# controller.net
KiCad netlist of a schematic drawn in EAGLE
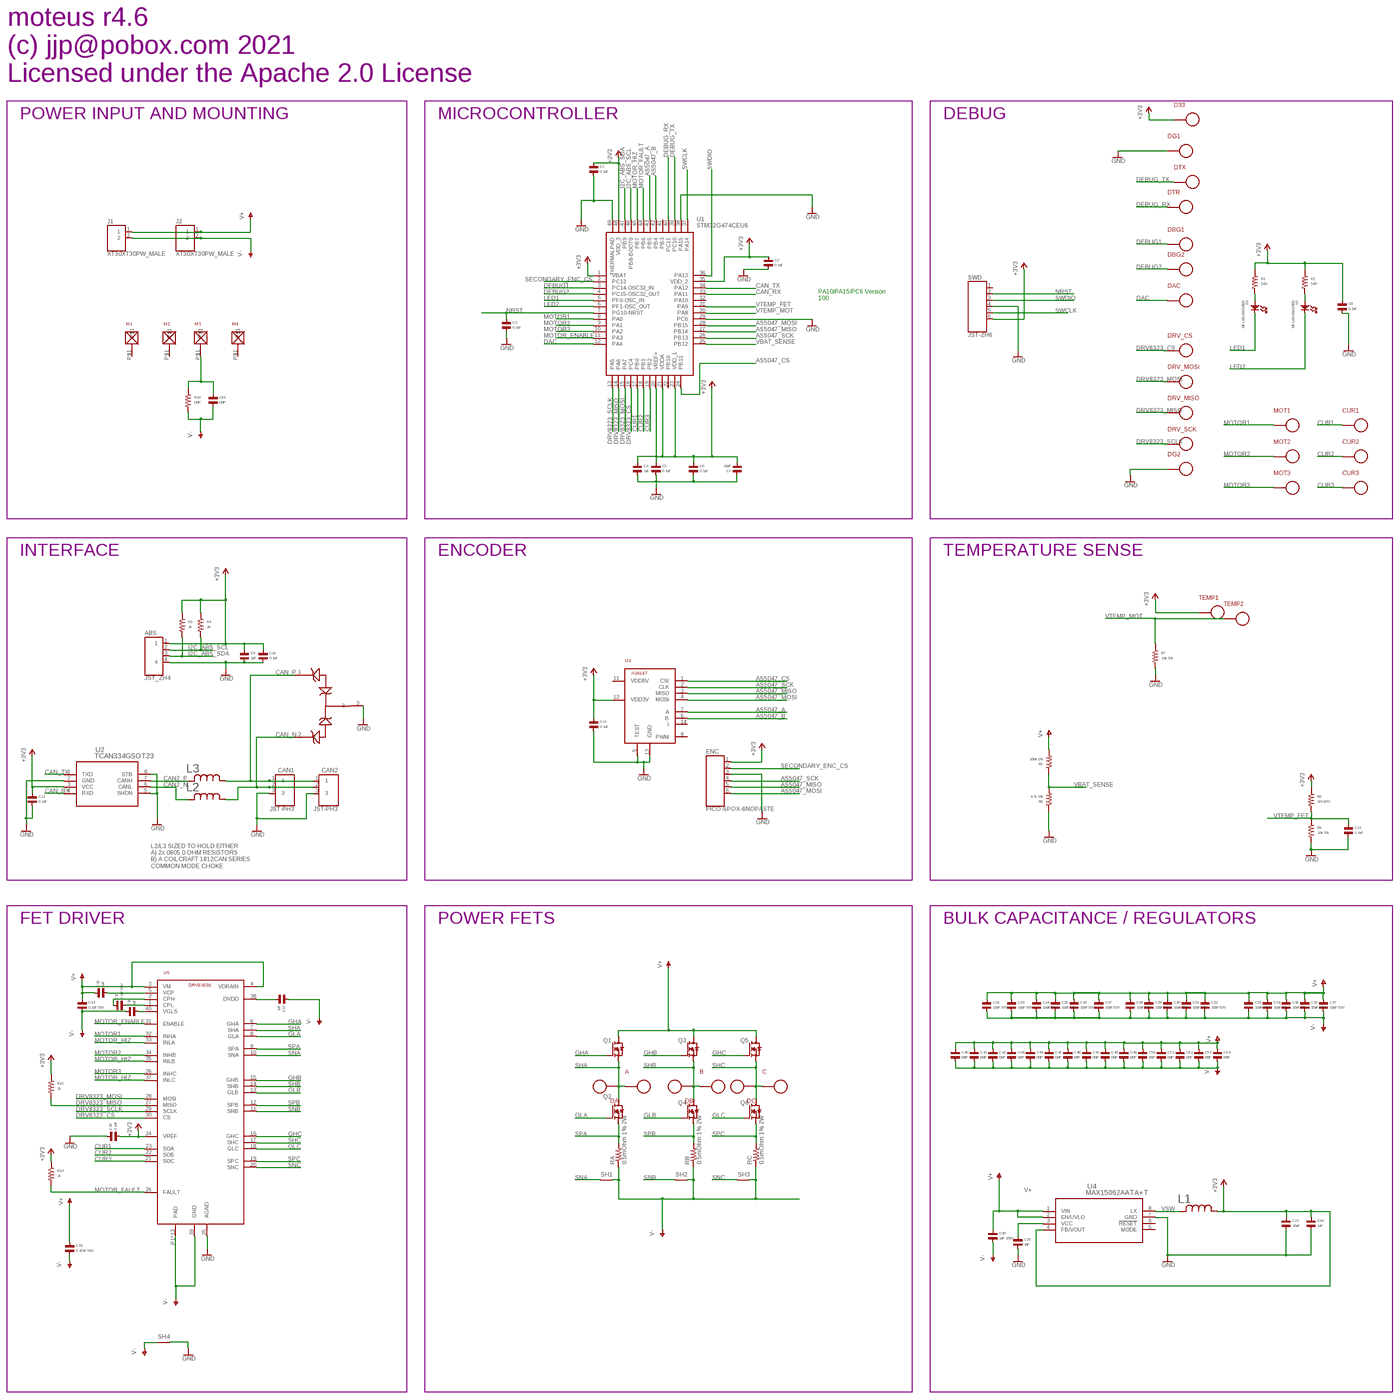
[diagram p0: schematic, sheet 1, overview]
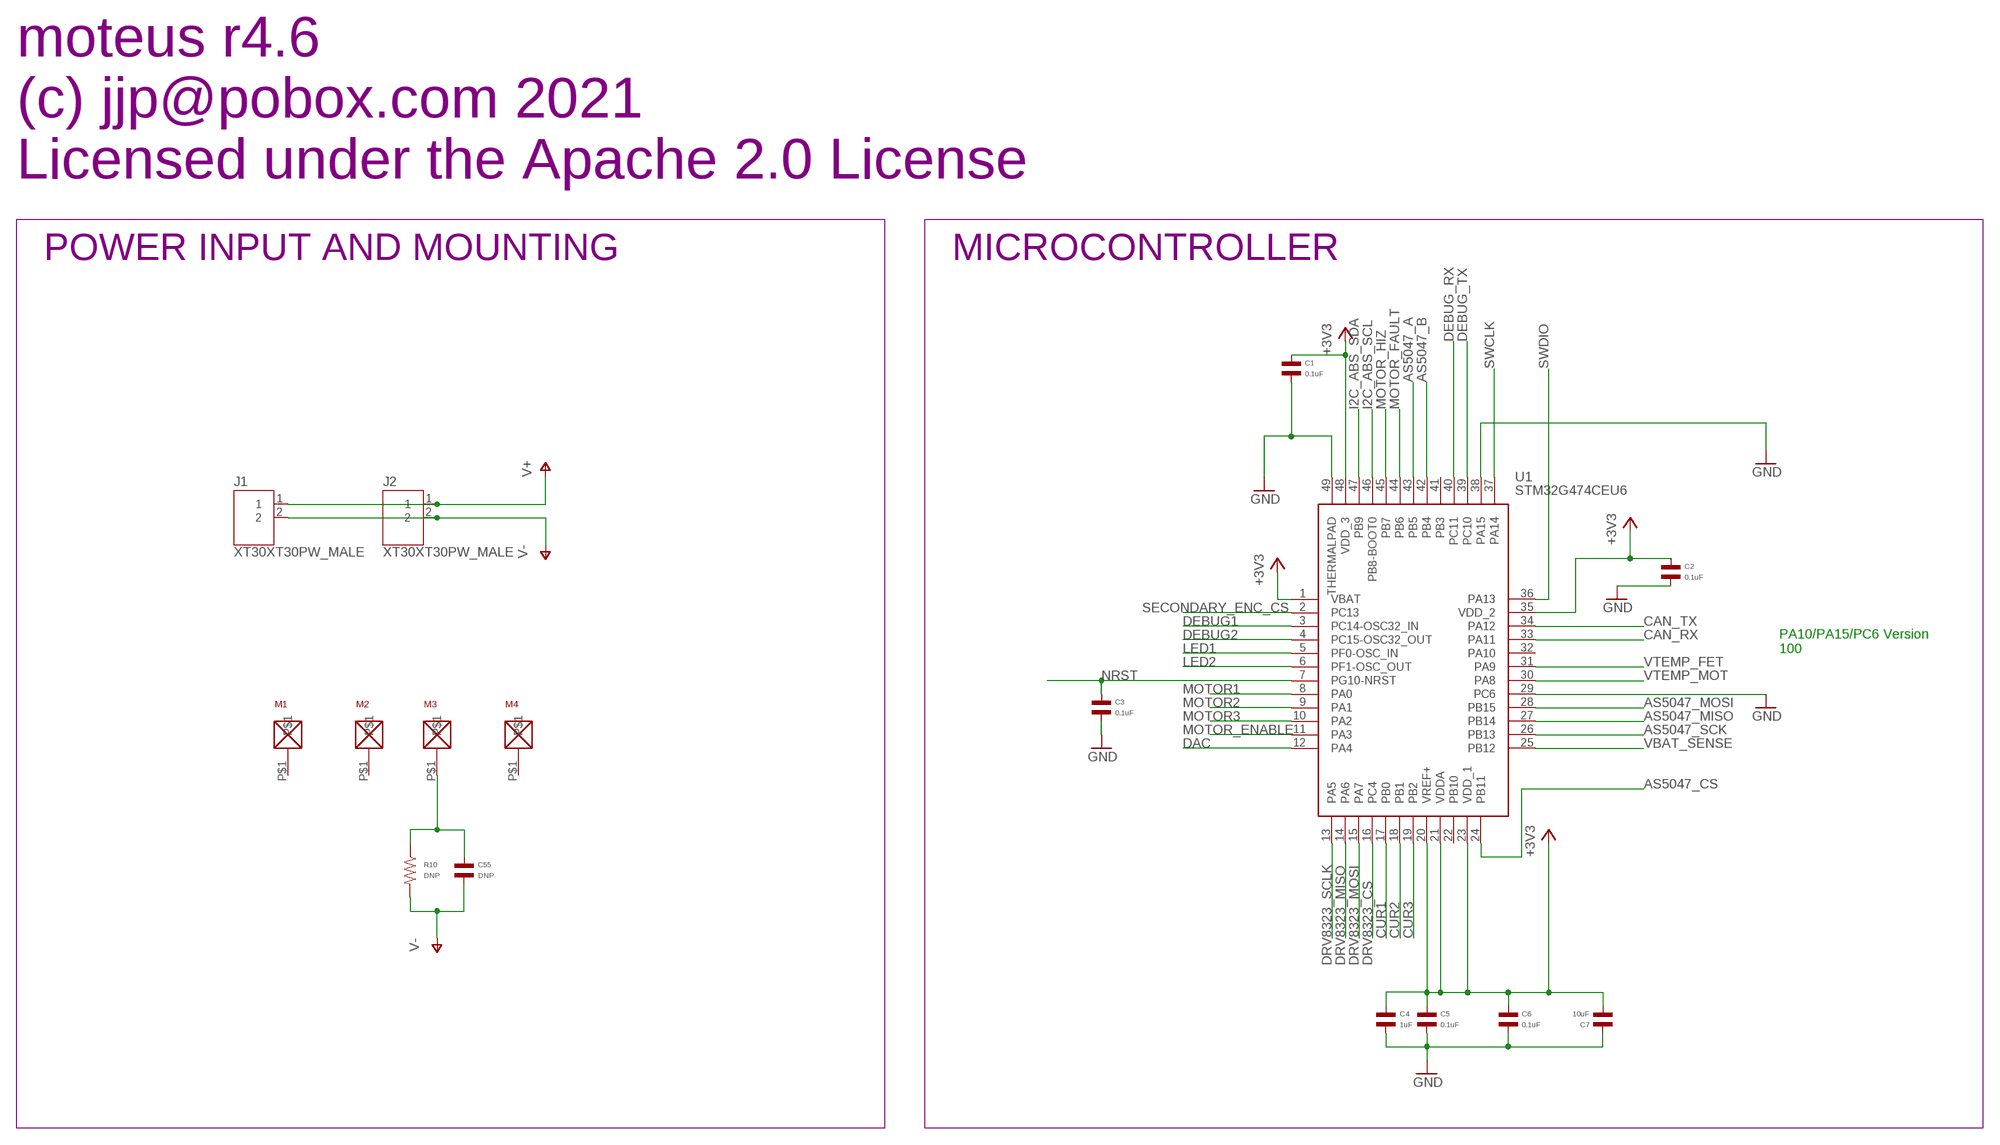
[diagram p1: schematic, sheet 1, part 1 of 4]
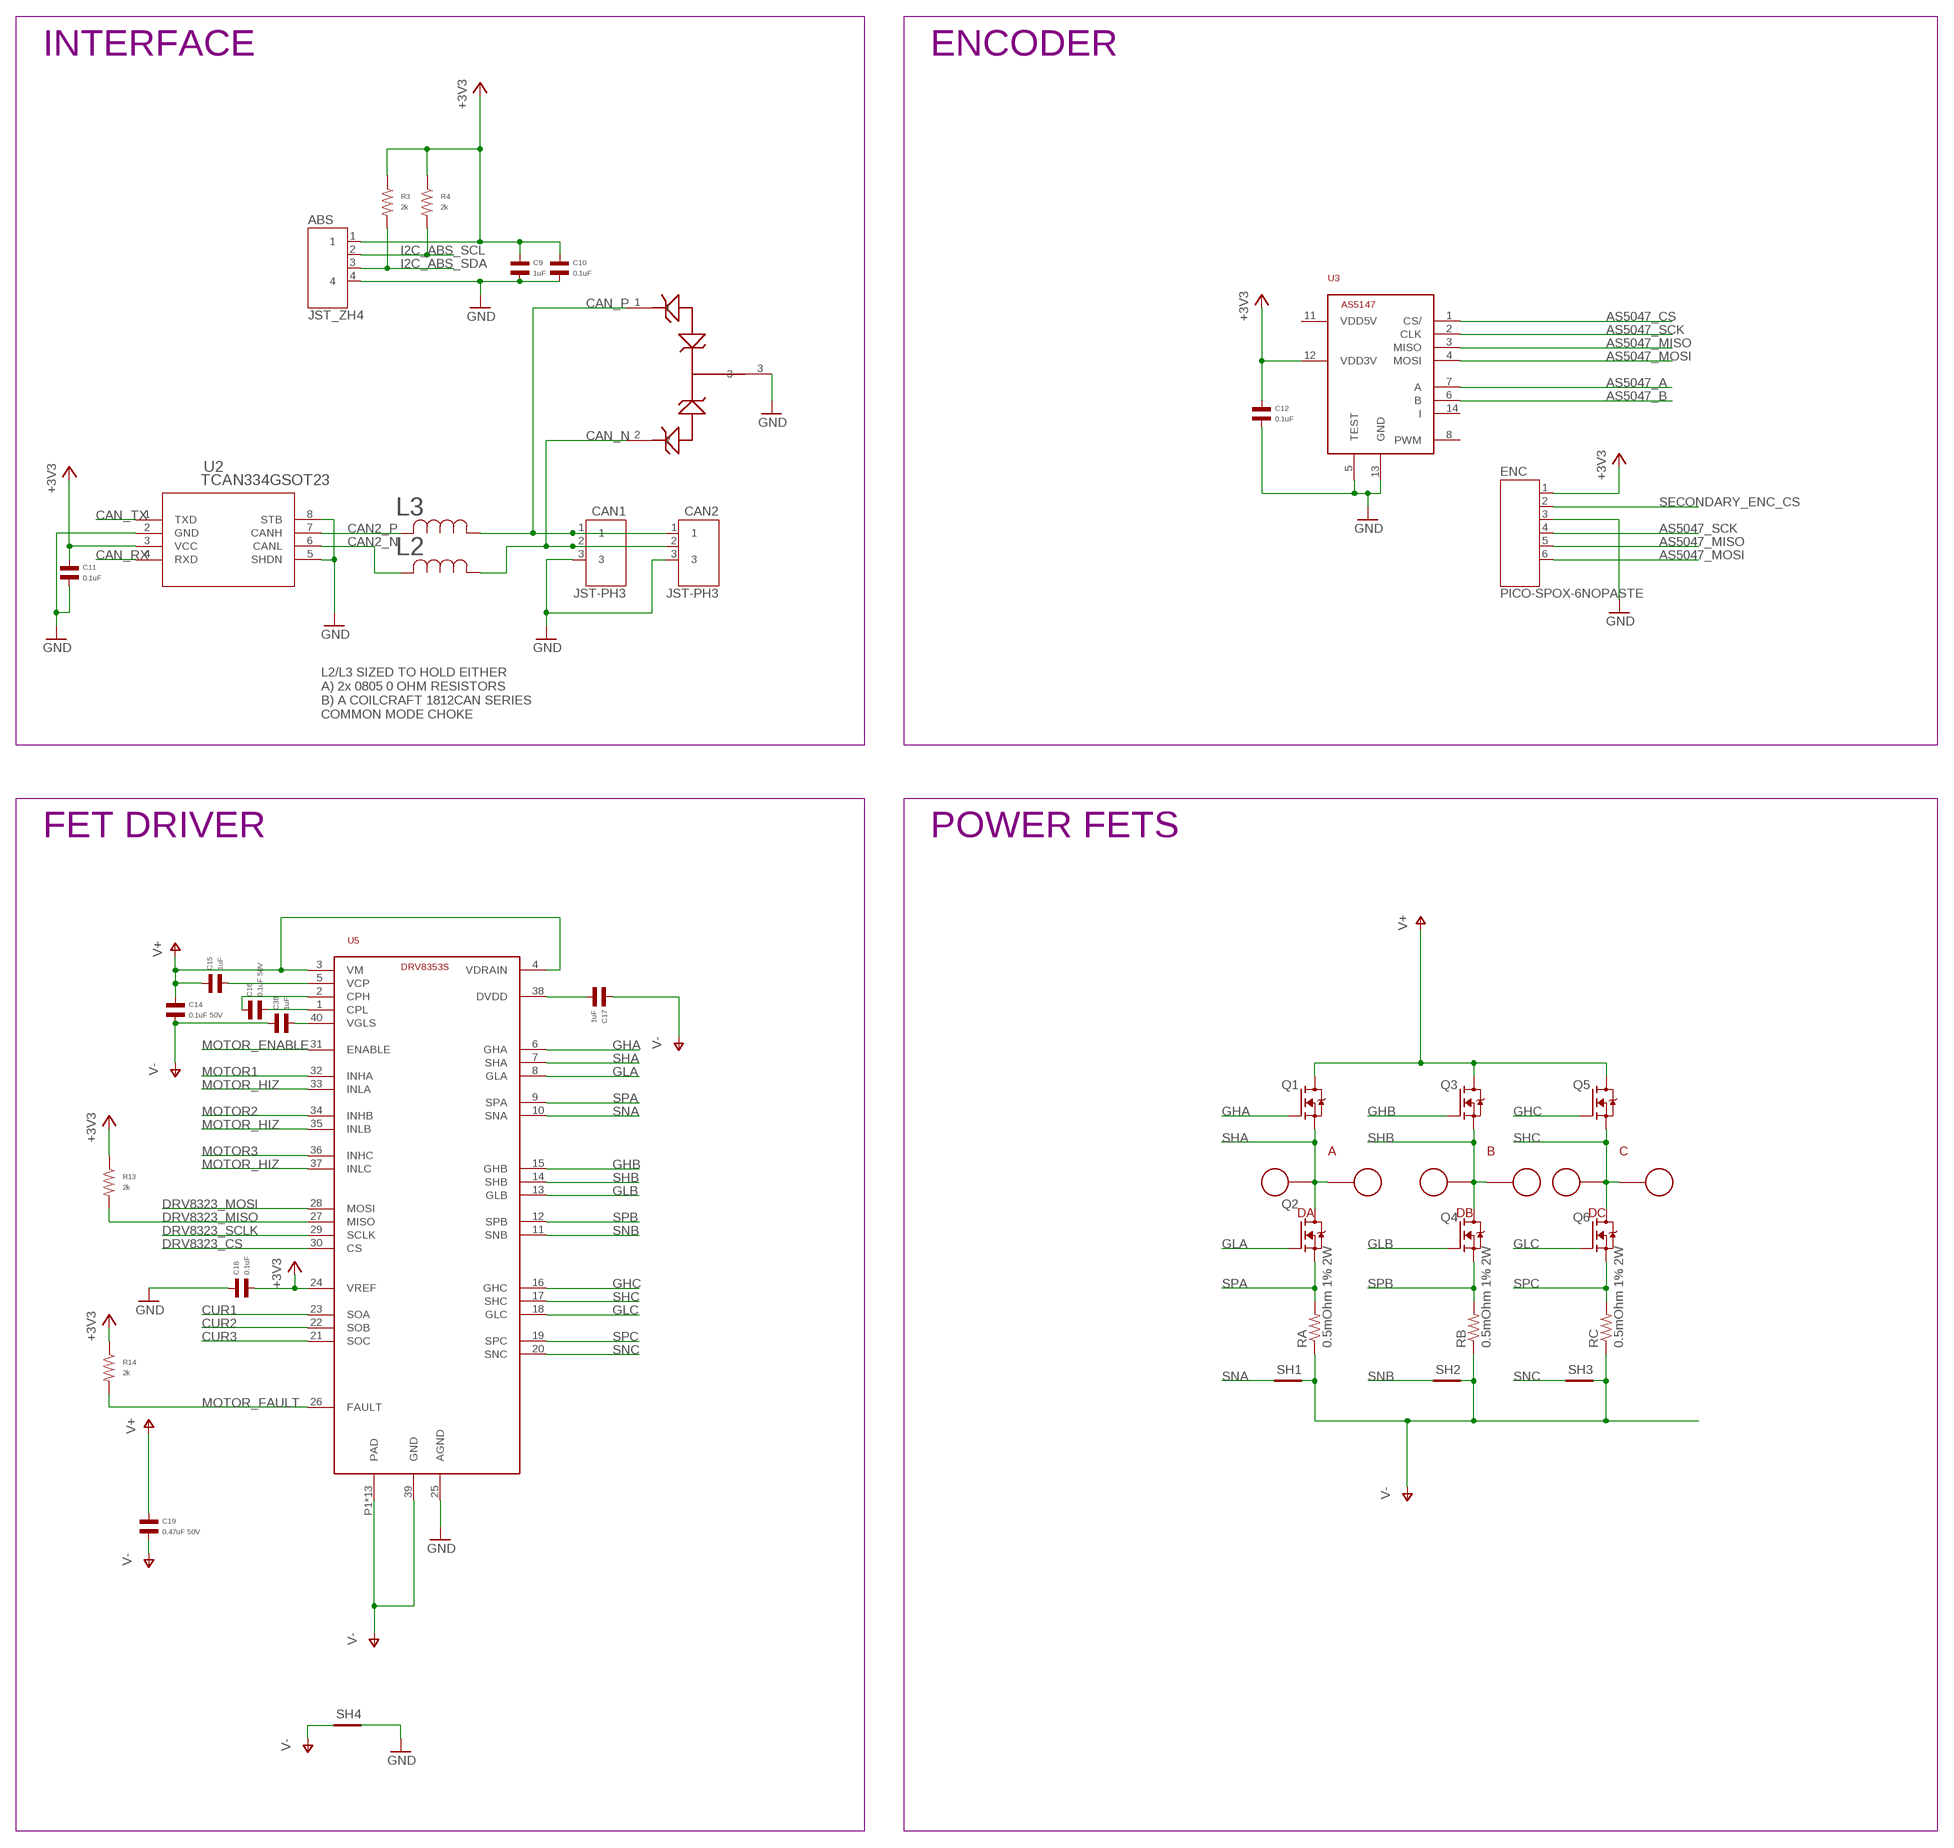
[diagram p2: schematic, sheet 1, part 2 of 4]
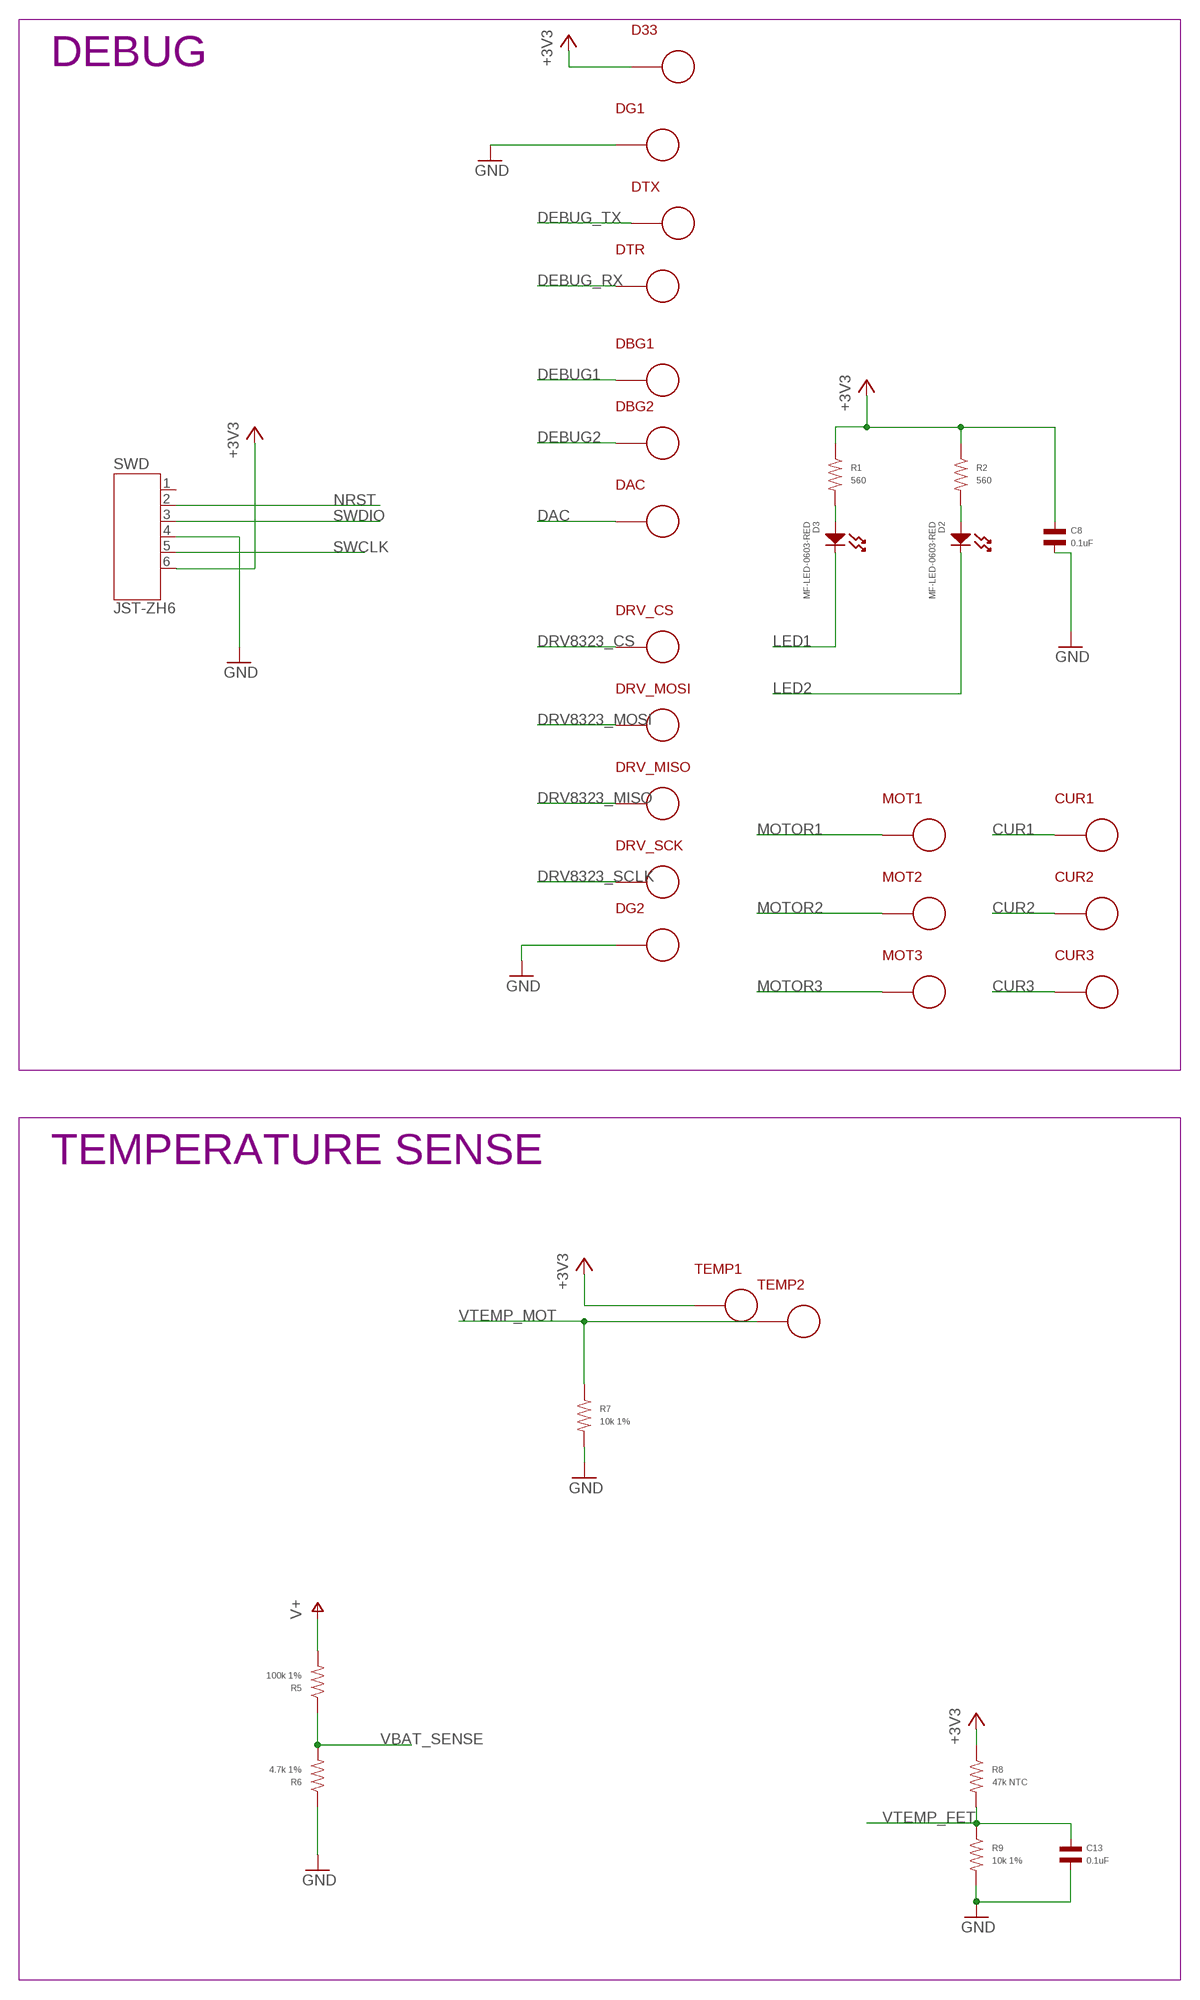
[diagram p3: schematic, sheet 1, part 3 of 4]
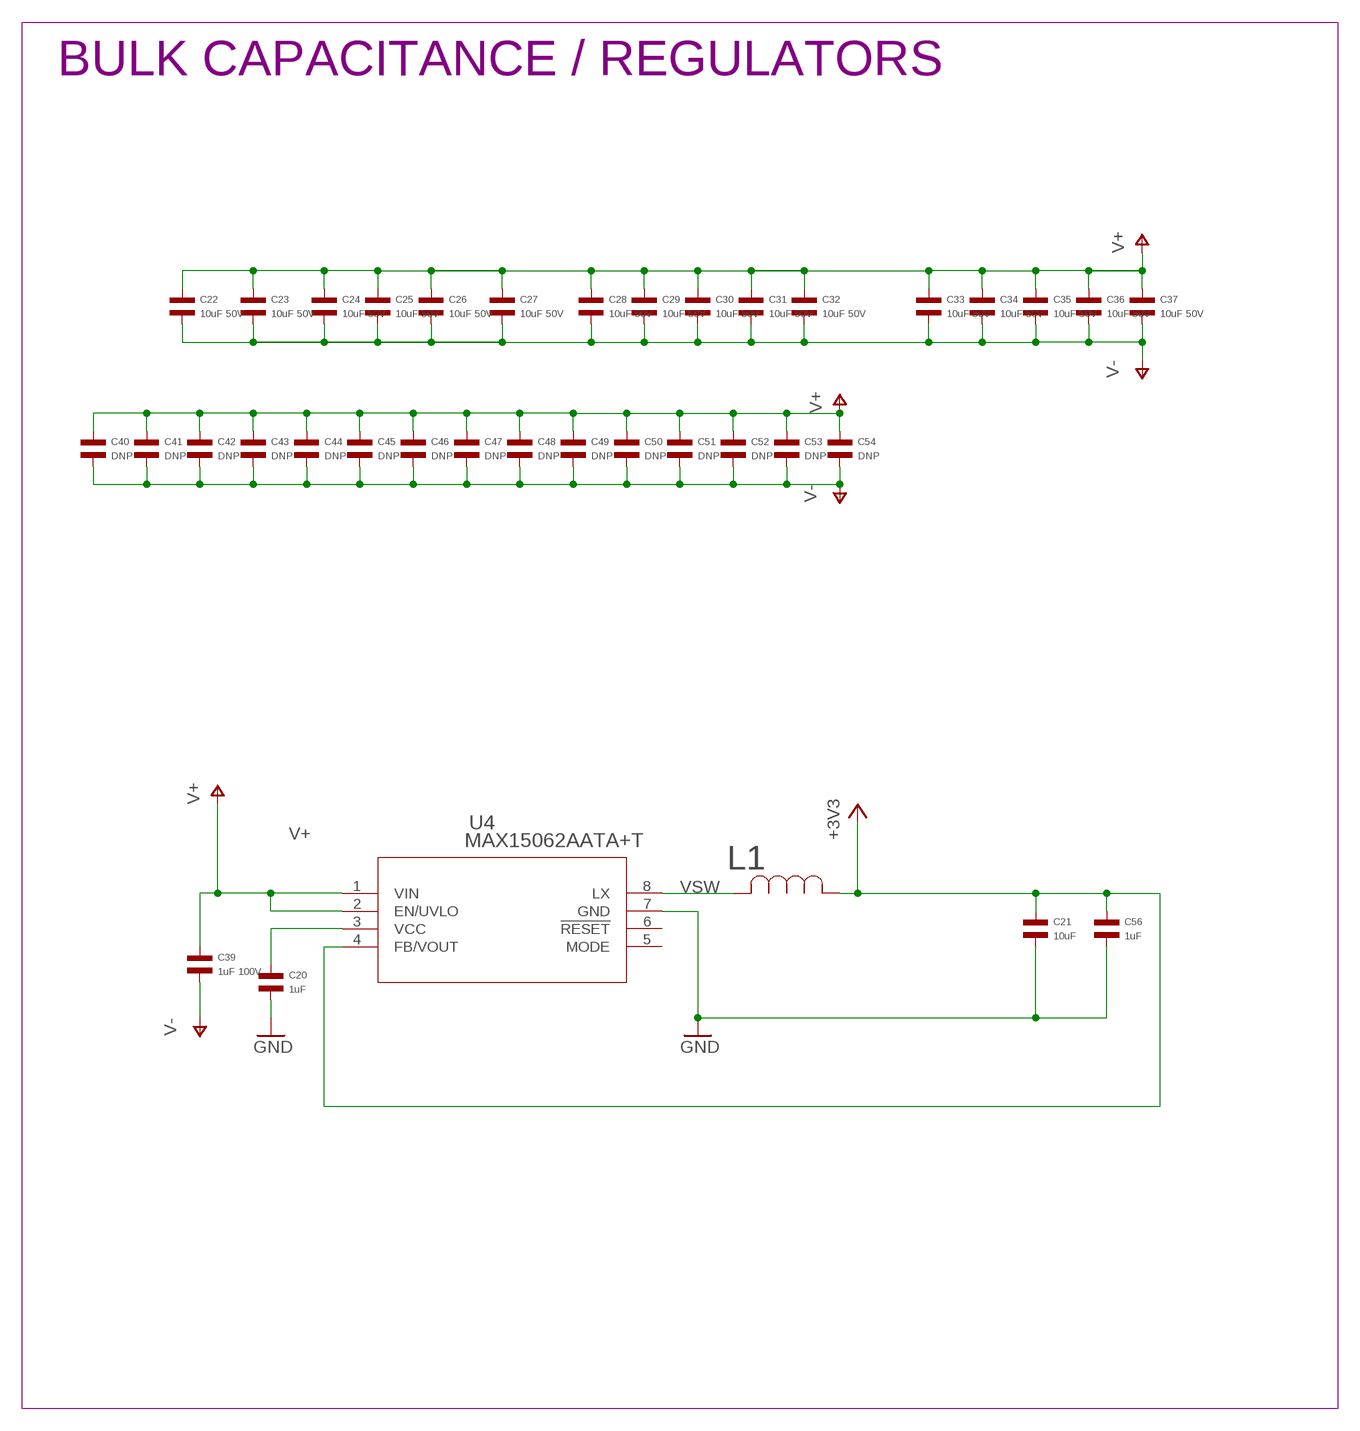
[diagram p4: schematic, sheet 1, part 4 of 4]

(export (version "E")
  (design (tool "Eeschema 10.0.6"))
  (components
    (comp (ref "A")
      (value "PAD16AWG_PAD")
      (footprint "eagle-import:16AWG_PAD")
      (libsource (lib "eagle-import") (part "PAD16AWG_PAD"))
    )
    (comp (ref "ABS")
      (value "JST_ZH4")
      (footprint "eagle-import:JST_S4B-ZR-SM4A-TF(LF)(SN)")
      (fields (field (name "MF") "JST") (field (name "MPN") "S4B-ZR-SM4A-TF(LF)(SN)"))
      (libsource (lib "eagle-import") (part "JST_ZH4"))
    )
    (comp (ref "B")
      (value "PAD16AWG_PAD")
      (footprint "eagle-import:16AWG_PAD")
      (libsource (lib "eagle-import") (part "PAD16AWG_PAD"))
    )
    (comp (ref "C")
      (value "PAD16AWG_PAD")
      (footprint "eagle-import:16AWG_PAD")
      (libsource (lib "eagle-import") (part "PAD16AWG_PAD"))
    )
    (comp (ref "C1")
      (value "0.1uF")
      (footprint "eagle-import:C0402")
      (fields (field (name "HOUSEPART") "YES") (field (name "MPN") "MF-CAP-0402-0.1uF"))
      (libsource (lib "eagle-import") (part "mfpassives_CAPACITOR_NP_0402"))
    )
    (comp (ref "C2")
      (value "0.1uF")
      (footprint "eagle-import:C0402")
      (fields (field (name "HOUSEPART") "YES") (field (name "MPN") "MF-CAP-0402-0.1uF"))
      (libsource (lib "eagle-import") (part "mfpassives_CAPACITOR_NP_0402"))
    )
    (comp (ref "C3")
      (value "0.1uF")
      (footprint "eagle-import:C0402")
      (fields (field (name "HOUSEPART") "YES") (field (name "MPN") "MF-CAP-0402-0.1uF"))
      (libsource (lib "eagle-import") (part "mfpassives_CAPACITOR_NP_0402"))
    )
    (comp (ref "C4")
      (value "1uF")
      (footprint "eagle-import:C0402")
      (fields (field (name "HOUSEPART") "YES") (field (name "MPN") "MF-CAP-0402-1uF"))
      (libsource (lib "eagle-import") (part "mfpassives_CAPACITOR_NP_0402"))
    )
    (comp (ref "C5")
      (value "0.1uF")
      (footprint "eagle-import:C0402")
      (fields (field (name "HOUSEPART") "YES") (field (name "MPN") "MF-CAP-0402-0.1uF"))
      (libsource (lib "eagle-import") (part "mfpassives_CAPACITOR_NP_0402"))
    )
    (comp (ref "C6")
      (value "0.1uF")
      (footprint "eagle-import:C0402")
      (fields (field (name "HOUSEPART") "YES") (field (name "MPN") "MF-CAP-0402-0.1uF"))
      (libsource (lib "eagle-import") (part "mfpassives_CAPACITOR_NP_0402"))
    )
    (comp (ref "C7")
      (value "10uF")
      (footprint "eagle-import:C1206")
      (fields (field (name "HOUSEPART") "YES") (field (name "MPN") "MF-CAP-1206-10uF"))
      (libsource (lib "eagle-import") (part "mfpassives_CAPACITOR_NP_1206"))
    )
    (comp (ref "C8")
      (value "0.1uF")
      (footprint "eagle-import:C0402")
      (fields (field (name "HOUSEPART") "YES") (field (name "MPN") "MF-CAP-0402-0.1uF"))
      (libsource (lib "eagle-import") (part "mfpassives_CAPACITOR_NP_0402"))
    )
    (comp (ref "C9")
      (value "1uF")
      (footprint "eagle-import:C0402")
      (fields (field (name "HOUSEPART") "YES") (field (name "MPN") "MF-CAP-0402-1uF"))
      (libsource (lib "eagle-import") (part "mfpassives_CAPACITOR_NP_0402"))
    )
    (comp (ref "C10")
      (value "0.1uF")
      (footprint "eagle-import:C0402")
      (fields (field (name "HOUSEPART") "YES") (field (name "MPN") "MF-CAP-0402-0.1uF"))
      (libsource (lib "eagle-import") (part "mfpassives_CAPACITOR_NP_0402"))
    )
    (comp (ref "C11")
      (value "0.1uF")
      (footprint "eagle-import:C0402")
      (fields (field (name "HOUSEPART") "YES") (field (name "MPN") "MF-CAP-0402-0.1uF"))
      (libsource (lib "eagle-import") (part "mfpassives_CAPACITOR_NP_0402"))
    )
    (comp (ref "C12")
      (value "0.1uF")
      (footprint "eagle-import:C0402")
      (fields (field (name "HOUSEPART") "YES") (field (name "MPN") "MF-CAP-0402-0.1uF"))
      (libsource (lib "eagle-import") (part "mfpassives_CAPACITOR_NP_0402"))
    )
    (comp (ref "C13")
      (value "0.1uF")
      (footprint "eagle-import:C0402")
      (fields (field (name "HOUSEPART") "YES") (field (name "MPN") "MF-CAP-0402-0.1uF"))
      (libsource (lib "eagle-import") (part "mfpassives_CAPACITOR_NP_0402"))
    )
    (comp (ref "C14")
      (value "0.1uF 50V")
      (footprint "eagle-import:C0402")
      (fields (field (name "MF") "TDK") (field (name "MPN") "CGA2B3X7R1H104K050BB"))
      (libsource (lib "eagle-import") (part "mfpassives_CAPACITOR_NP_0402"))
    )
    (comp (ref "C15")
      (value "1uF")
      (footprint "eagle-import:C0402")
      (fields (field (name "HOUSEPART") "YES") (field (name "MPN") "MF-CAP-0402-1uF"))
      (libsource (lib "eagle-import") (part "mfpassives_CAPACITOR_NP_0402"))
    )
    (comp (ref "C16")
      (value "0.1uF 50V")
      (footprint "eagle-import:C0402")
      (fields (field (name "MF") "TDK") (field (name "MPN") "CGA2B3X7R1H104K050BB"))
      (libsource (lib "eagle-import") (part "mfpassives_CAPACITOR_NP_0402"))
    )
    (comp (ref "C17")
      (value "1uF")
      (footprint "eagle-import:C0402")
      (fields (field (name "HOUSEPART") "YES") (field (name "MPN") "MF-CAP-0402-1uF"))
      (libsource (lib "eagle-import") (part "mfpassives_CAPACITOR_NP_0402"))
    )
    (comp (ref "C18")
      (value "0.1uF")
      (footprint "eagle-import:C0402")
      (fields (field (name "HOUSEPART") "YES") (field (name "MPN") "MF-CAP-0402-0.1uF"))
      (libsource (lib "eagle-import") (part "mfpassives_CAPACITOR_NP_0402"))
    )
    (comp (ref "C19")
      (value "0.47uF 50V")
      (footprint "eagle-import:C0402")
      (fields (field (name "MF") "Murata") (field (name "MPN") "GRM155R61H474KE11D"))
      (libsource (lib "eagle-import") (part "mfpassives_CAPACITOR_NP_0402"))
    )
    (comp (ref "C20")
      (value "1uF")
      (footprint "eagle-import:C0603")
      (fields (field (name "HOUSEPART") "1") (field (name "MPN") "MF-CAP-0603-1uF"))
      (libsource (lib "eagle-import") (part "mfpassives_CAPACITOR_NP_0603"))
    )
    (comp (ref "C21")
      (value "10uF")
      (footprint "eagle-import:C1206")
      (fields (field (name "HOUSEPART") "1") (field (name "MPN") "MF-CAP-1206-10uF"))
      (libsource (lib "eagle-import") (part "mfpassives_CAPACITOR_NP_1206"))
    )
    (comp (ref "C22")
      (value "10uF 50V")
      (footprint "eagle-import:C1206")
      (fields (field (name "MF") "TDK") (field (name "MPN") "C3216X7R1H106K160AE"))
      (libsource (lib "eagle-import") (part "mfpassives_CAPACITOR_NP_1206"))
    )
    (comp (ref "C23")
      (value "10uF 50V")
      (footprint "eagle-import:C1206")
      (fields (field (name "MF") "TDK") (field (name "MPN") "C3216X7R1H106K160AE"))
      (libsource (lib "eagle-import") (part "mfpassives_CAPACITOR_NP_1206"))
    )
    (comp (ref "C24")
      (value "10uF 50V")
      (footprint "eagle-import:C1206")
      (fields (field (name "MF") "TDK") (field (name "MPN") "C3216X7R1H106K160AE"))
      (libsource (lib "eagle-import") (part "mfpassives_CAPACITOR_NP_1206"))
    )
    (comp (ref "C25")
      (value "10uF 50V")
      (footprint "eagle-import:C1206")
      (fields (field (name "MF") "TDK") (field (name "MPN") "C3216X7R1H106K160AE"))
      (libsource (lib "eagle-import") (part "mfpassives_CAPACITOR_NP_1206"))
    )
    (comp (ref "C26")
      (value "10uF 50V")
      (footprint "eagle-import:C1206")
      (fields (field (name "MF") "TDK") (field (name "MPN") "C3216X7R1H106K160AE"))
      (libsource (lib "eagle-import") (part "mfpassives_CAPACITOR_NP_1206"))
    )
    (comp (ref "C27")
      (value "10uF 50V")
      (footprint "eagle-import:C1206")
      (fields (field (name "MF") "TDK") (field (name "MPN") "C3216X7R1H106K160AE"))
      (libsource (lib "eagle-import") (part "mfpassives_CAPACITOR_NP_1206"))
    )
    (comp (ref "C28")
      (value "10uF 50V")
      (footprint "eagle-import:C1206")
      (fields (field (name "MF") "TDK") (field (name "MPN") "C3216X7R1H106K160AE"))
      (libsource (lib "eagle-import") (part "mfpassives_CAPACITOR_NP_1206"))
    )
    (comp (ref "C29")
      (value "10uF 50V")
      (footprint "eagle-import:C1206")
      (fields (field (name "MF") "TDK") (field (name "MPN") "C3216X7R1H106K160AE"))
      (libsource (lib "eagle-import") (part "mfpassives_CAPACITOR_NP_1206"))
    )
    (comp (ref "C30")
      (value "10uF 50V")
      (footprint "eagle-import:C1206")
      (fields (field (name "MF") "TDK") (field (name "MPN") "C3216X7R1H106K160AE"))
      (libsource (lib "eagle-import") (part "mfpassives_CAPACITOR_NP_1206"))
    )
    (comp (ref "C31")
      (value "10uF 50V")
      (footprint "eagle-import:C1206")
      (fields (field (name "MF") "TDK") (field (name "MPN") "C3216X7R1H106K160AE"))
      (libsource (lib "eagle-import") (part "mfpassives_CAPACITOR_NP_1206"))
    )
    (comp (ref "C32")
      (value "10uF 50V")
      (footprint "eagle-import:C1206")
      (fields (field (name "MF") "TDK") (field (name "MPN") "C3216X7R1H106K160AE"))
      (libsource (lib "eagle-import") (part "mfpassives_CAPACITOR_NP_1206"))
    )
    (comp (ref "C33")
      (value "10uF 50V")
      (footprint "eagle-import:C1206")
      (fields (field (name "MF") "TDK") (field (name "MPN") "C3216X7R1H106K160AE"))
      (libsource (lib "eagle-import") (part "mfpassives_CAPACITOR_NP_1206"))
    )
    (comp (ref "C34")
      (value "10uF 50V")
      (footprint "eagle-import:C1206")
      (fields (field (name "MF") "TDK") (field (name "MPN") "C3216X7R1H106K160AE"))
      (libsource (lib "eagle-import") (part "mfpassives_CAPACITOR_NP_1206"))
    )
    (comp (ref "C35")
      (value "10uF 50V")
      (footprint "eagle-import:C1206")
      (fields (field (name "MF") "TDK") (field (name "MPN") "C3216X7R1H106K160AE"))
      (libsource (lib "eagle-import") (part "mfpassives_CAPACITOR_NP_1206"))
    )
    (comp (ref "C36")
      (value "10uF 50V")
      (footprint "eagle-import:C1206")
      (fields (field (name "MF") "TDK") (field (name "MPN") "C3216X7R1H106K160AE"))
      (libsource (lib "eagle-import") (part "mfpassives_CAPACITOR_NP_1206"))
    )
    (comp (ref "C37")
      (value "10uF 50V")
      (footprint "eagle-import:C1206")
      (fields (field (name "MF") "TDK") (field (name "MPN") "C3216X7R1H106K160AE"))
      (libsource (lib "eagle-import") (part "mfpassives_CAPACITOR_NP_1206"))
    )
    (comp (ref "C38")
      (value "1uF")
      (footprint "eagle-import:C0402")
      (fields (field (name "HOUSEPART") "YES") (field (name "MPN") "MF-CAP-0402-1uF"))
      (libsource (lib "eagle-import") (part "mfpassives_CAPACITOR_NP_0402"))
    )
    (comp (ref "C39")
      (value "1uF 100V")
      (footprint "eagle-import:C0805")
      (fields (field (name "MF") "MURATA") (field (name "MPN") "GCM21BC72A105KE36L"))
      (libsource (lib "eagle-import") (part "mfpassives_CAPACITOR_NP_0805"))
    )
    (comp (ref "C40")
      (value "DNP")
      (footprint "eagle-import:C1206_NOCREAM")
      (libsource (lib "eagle-import") (part "CAPACITOR_NP_1206_NOCREAM"))
    )
    (comp (ref "C41")
      (value "DNP")
      (footprint "eagle-import:C1206_NOCREAM")
      (libsource (lib "eagle-import") (part "CAPACITOR_NP_1206_NOCREAM"))
    )
    (comp (ref "C42")
      (value "DNP")
      (footprint "eagle-import:C1206_NOCREAM")
      (libsource (lib "eagle-import") (part "CAPACITOR_NP_1206_NOCREAM"))
    )
    (comp (ref "C43")
      (value "DNP")
      (footprint "eagle-import:C1206_NOCREAM")
      (libsource (lib "eagle-import") (part "CAPACITOR_NP_1206_NOCREAM"))
    )
    (comp (ref "C44")
      (value "DNP")
      (footprint "eagle-import:C1206_NOCREAM")
      (libsource (lib "eagle-import") (part "CAPACITOR_NP_1206_NOCREAM"))
    )
    (comp (ref "C45")
      (value "DNP")
      (footprint "eagle-import:C1206_NOCREAM")
      (libsource (lib "eagle-import") (part "CAPACITOR_NP_1206_NOCREAM"))
    )
    (comp (ref "C46")
      (value "DNP")
      (footprint "eagle-import:C1206_NOCREAM")
      (libsource (lib "eagle-import") (part "CAPACITOR_NP_1206_NOCREAM"))
    )
    (comp (ref "C47")
      (value "DNP")
      (footprint "eagle-import:C1206_NOCREAM")
      (libsource (lib "eagle-import") (part "CAPACITOR_NP_1206_NOCREAM"))
    )
    (comp (ref "C48")
      (value "DNP")
      (footprint "eagle-import:C1206_NOCREAM")
      (libsource (lib "eagle-import") (part "CAPACITOR_NP_1206_NOCREAM"))
    )
    (comp (ref "C49")
      (value "DNP")
      (footprint "eagle-import:C1206_NOCREAM")
      (libsource (lib "eagle-import") (part "CAPACITOR_NP_1206_NOCREAM"))
    )
    (comp (ref "C50")
      (value "DNP")
      (footprint "eagle-import:C1206_NOCREAM")
      (libsource (lib "eagle-import") (part "CAPACITOR_NP_1206_NOCREAM"))
    )
    (comp (ref "C51")
      (value "DNP")
      (footprint "eagle-import:C1206_NOCREAM")
      (libsource (lib "eagle-import") (part "CAPACITOR_NP_1206_NOCREAM"))
    )
    (comp (ref "C52")
      (value "DNP")
      (footprint "eagle-import:C1206_NOCREAM")
      (libsource (lib "eagle-import") (part "CAPACITOR_NP_1206_NOCREAM"))
    )
    (comp (ref "C53")
      (value "DNP")
      (footprint "eagle-import:C1206_NOCREAM")
      (libsource (lib "eagle-import") (part "CAPACITOR_NP_1206_NOCREAM"))
    )
    (comp (ref "C54")
      (value "DNP")
      (footprint "eagle-import:C1206_NOCREAM")
      (libsource (lib "eagle-import") (part "CAPACITOR_NP_1206_NOCREAM"))
    )
    (comp (ref "C55")
      (value "DNP")
      (footprint "eagle-import:C0402")
      (fields (field (name "POPULATE") "0"))
      (libsource (lib "eagle-import") (part "mfpassives_CAPACITOR_NP_0402"))
    )
    (comp (ref "C56")
      (value "1uF")
      (footprint "eagle-import:C0402")
      (fields (field (name "HOUSEPART") "YES") (field (name "MPN") "MF-CAP-0402-1uF"))
      (libsource (lib "eagle-import") (part "mfpassives_CAPACITOR_NP_0402"))
    )
    (comp (ref "CAN1")
      (value "JST-PH3")
      (footprint "eagle-import:JST_S3B-PH-SM4-TB(LF)(SN)")
      (fields (field (name "MF") "JST") (field (name "MPN") "S3B-PH-SM4-TB(LF)(SN)"))
      (libsource (lib "eagle-import") (part "JST-PH3"))
    )
    (comp (ref "CAN2")
      (value "JST-PH3")
      (footprint "eagle-import:JST_S3B-PH-SM4-TB(LF)(SN)")
      (fields (field (name "MF") "JST") (field (name "MPN") "S3B-PH-SM4-TB(LF)(SN)"))
      (libsource (lib "eagle-import") (part "JST-PH3"))
    )
    (comp (ref "CUR1")
      (value "PAD24AWG_PAD")
      (footprint "eagle-import:24AWG_PAD")
      (libsource (lib "eagle-import") (part "PAD24AWG_PAD"))
    )
    (comp (ref "CUR2")
      (value "PAD24AWG_PAD")
      (footprint "eagle-import:24AWG_PAD")
      (libsource (lib "eagle-import") (part "PAD24AWG_PAD"))
    )
    (comp (ref "CUR3")
      (value "PAD24AWG_PAD")
      (footprint "eagle-import:24AWG_PAD")
      (libsource (lib "eagle-import") (part "PAD24AWG_PAD"))
    )
    (comp (ref "D2")
      (value "MF-LED-0603-RED")
      (footprint "eagle-import:LED0603")
      (fields (field (name "HOUSEPART") "YES") (field (name "MPN") "MF-LED-0603-GREEN"))
      (libsource (lib "eagle-import") (part "LED_SINGLE-0603-RED"))
    )
    (comp (ref "D3")
      (value "MF-LED-0603-RED")
      (footprint "eagle-import:LED0603")
      (fields (field (name "HOUSEPART") "YES"))
      (libsource (lib "eagle-import") (part "LED_SINGLE-0603-RED"))
    )
    (comp (ref "D4")
      (value "DUAL_TVS")
      (footprint "eagle-import:SOT23-3")
      (fields (field (name "MPN") "CDSOT23-0502B"))
      (libsource (lib "eagle-import") (part "DUAL_TVS"))
    )
    (comp (ref "D33")
      (value "PAD24AWG_PAD")
      (footprint "eagle-import:24AWG_PAD")
      (libsource (lib "eagle-import") (part "PAD24AWG_PAD"))
    )
    (comp (ref "DA")
      (value "PAD24AWG_PAD")
      (footprint "eagle-import:24AWG_PAD")
      (libsource (lib "eagle-import") (part "PAD24AWG_PAD"))
    )
    (comp (ref "DAC")
      (value "PAD24AWG_PAD")
      (footprint "eagle-import:24AWG_PAD")
      (libsource (lib "eagle-import") (part "PAD24AWG_PAD"))
    )
    (comp (ref "DB")
      (value "PAD24AWG_PAD")
      (footprint "eagle-import:24AWG_PAD")
      (libsource (lib "eagle-import") (part "PAD24AWG_PAD"))
    )
    (comp (ref "DBG1")
      (value "PAD24AWG_PAD")
      (footprint "eagle-import:24AWG_PAD")
      (libsource (lib "eagle-import") (part "PAD24AWG_PAD"))
    )
    (comp (ref "DBG2")
      (value "PAD24AWG_PAD")
      (footprint "eagle-import:24AWG_PAD")
      (libsource (lib "eagle-import") (part "PAD24AWG_PAD"))
    )
    (comp (ref "DC")
      (value "PAD24AWG_PAD")
      (footprint "eagle-import:24AWG_PAD")
      (libsource (lib "eagle-import") (part "PAD24AWG_PAD"))
    )
    (comp (ref "DG1")
      (value "PAD24AWG_PAD")
      (footprint "eagle-import:24AWG_PAD")
      (libsource (lib "eagle-import") (part "PAD24AWG_PAD"))
    )
    (comp (ref "DG2")
      (value "PAD24AWG_PAD")
      (footprint "eagle-import:24AWG_PAD")
      (libsource (lib "eagle-import") (part "PAD24AWG_PAD"))
    )
    (comp (ref "DRV_CS")
      (value "PAD24AWG_PAD")
      (footprint "eagle-import:24AWG_PAD")
      (libsource (lib "eagle-import") (part "PAD24AWG_PAD"))
    )
    (comp (ref "DRV_MISO")
      (value "PAD24AWG_PAD")
      (footprint "eagle-import:24AWG_PAD")
      (libsource (lib "eagle-import") (part "PAD24AWG_PAD"))
    )
    (comp (ref "DRV_MOSI")
      (value "PAD24AWG_PAD")
      (footprint "eagle-import:24AWG_PAD")
      (libsource (lib "eagle-import") (part "PAD24AWG_PAD"))
    )
    (comp (ref "DRV_SCK")
      (value "PAD24AWG_PAD")
      (footprint "eagle-import:24AWG_PAD")
      (libsource (lib "eagle-import") (part "PAD24AWG_PAD"))
    )
    (comp (ref "DTR")
      (value "PAD24AWG_PAD")
      (footprint "eagle-import:24AWG_PAD")
      (libsource (lib "eagle-import") (part "PAD24AWG_PAD"))
    )
    (comp (ref "DTX")
      (value "PAD24AWG_PAD")
      (footprint "eagle-import:24AWG_PAD")
      (libsource (lib "eagle-import") (part "PAD24AWG_PAD"))
    )
    (comp (ref "ENC")
      (value "PICO-SPOX-6NOPASTE")
      (footprint "eagle-import:PICO-SPOX-SMT-RA-6-NOPASTE")
      (libsource (lib "eagle-import") (part "PICO-SPOX-6NOPASTE"))
    )
    (comp (ref "J1")
      (value "XT30XT30PW_MALE")
      (footprint "eagle-import:XT30PW_MALE")
      (libsource (lib "eagle-import") (part "XT30XT30PW_MALE"))
    )
    (comp (ref "J2")
      (value "XT30XT30PW_MALE")
      (footprint "eagle-import:XT30PW_MALE")
      (libsource (lib "eagle-import") (part "XT30XT30PW_MALE"))
    )
    (comp (ref "L1")
      (value "SRN4018-220M")
      (footprint "eagle-import:IND_BOURNS_SRN4018")
      (fields
        (field (name "MANUFACTURER_PART_NUMBER") "SRN4018220M")
        (field (name "MANUFACTURER_PART_NUMBER_1") "SRN4018-330M")
        (field (name "MPN") "SRN4018-330M")
      )
      (libsource (lib "eagle-import") (part "SRN4018-220M"))
    )
    (comp (ref "L2")
      (value "HALF_CHOKE")
      (footprint "eagle-import:1812_COMMON_HALF")
      (fields (field (name "MPN") "MF-RES-0805-0"))
      (libsource (lib "eagle-import") (part "HALF_CHOKE"))
    )
    (comp (ref "L3")
      (value "HALF_CHOKE")
      (footprint "eagle-import:1812_COMMON_HALF")
      (fields (field (name "MPN") "MF-RES-0805-0"))
      (libsource (lib "eagle-import") (part "HALF_CHOKE"))
    )
    (comp (ref "M1")
      (value "MOUNT")
      (footprint "eagle-import:M2.5MOUNT")
      (libsource (lib "eagle-import") (part "MOUNT"))
    )
    (comp (ref "M2")
      (value "MOUNT")
      (footprint "eagle-import:M2.5MOUNT")
      (libsource (lib "eagle-import") (part "MOUNT"))
    )
    (comp (ref "M3")
      (value "MOUNT")
      (footprint "eagle-import:M2.5MOUNT")
      (libsource (lib "eagle-import") (part "MOUNT"))
    )
    (comp (ref "M4")
      (value "MOUNT")
      (footprint "eagle-import:M2.5MOUNT")
      (libsource (lib "eagle-import") (part "MOUNT"))
    )
    (comp (ref "MOT1")
      (value "PAD24AWG_PAD")
      (footprint "eagle-import:24AWG_PAD")
      (libsource (lib "eagle-import") (part "PAD24AWG_PAD"))
    )
    (comp (ref "MOT2")
      (value "PAD24AWG_PAD")
      (footprint "eagle-import:24AWG_PAD")
      (libsource (lib "eagle-import") (part "PAD24AWG_PAD"))
    )
    (comp (ref "MOT3")
      (value "PAD24AWG_PAD")
      (footprint "eagle-import:24AWG_PAD")
      (libsource (lib "eagle-import") (part "PAD24AWG_PAD"))
    )
    (comp (ref "Q1")
      (value "TPH1R204PLSOP_ADVANCE_8")
      (footprint "eagle-import:SOP_ADVANCE_8")
      (fields
        (field (name "MF") "Toshiba")
        (field (name "MPN") "TPH1R204PL")
        (field (name "MF_1") "Toshiba")
        (field (name "MPN_1") "TPH2R506PL,L1Q")
      )
      (libsource (lib "eagle-import") (part "TPH1R204PLSOP_ADVANCE_8"))
    )
    (comp (ref "Q2")
      (value "TPH1R204PLSOP_ADVANCE_8")
      (footprint "eagle-import:SOP_ADVANCE_8")
      (fields
        (field (name "MF") "Toshiba")
        (field (name "MPN") "TPH1R204PL")
        (field (name "MF_1") "Toshiba")
        (field (name "MPN_1") "TPH2R506PL,L1Q")
      )
      (libsource (lib "eagle-import") (part "TPH1R204PLSOP_ADVANCE_8"))
    )
    (comp (ref "Q3")
      (value "TPH1R204PLSOP_ADVANCE_8")
      (footprint "eagle-import:SOP_ADVANCE_8")
      (fields
        (field (name "MF") "Toshiba")
        (field (name "MPN") "TPH1R204PL")
        (field (name "MF_1") "Toshiba")
        (field (name "MPN_1") "TPH2R506PL,L1Q")
      )
      (libsource (lib "eagle-import") (part "TPH1R204PLSOP_ADVANCE_8"))
    )
    (comp (ref "Q4")
      (value "TPH1R204PLSOP_ADVANCE_8")
      (footprint "eagle-import:SOP_ADVANCE_8")
      (fields
        (field (name "MF") "Toshiba")
        (field (name "MPN") "TPH1R204PL")
        (field (name "MF_1") "Toshiba")
        (field (name "MPN_1") "TPH2R506PL,L1Q")
      )
      (libsource (lib "eagle-import") (part "TPH1R204PLSOP_ADVANCE_8"))
    )
    (comp (ref "Q5")
      (value "TPH1R204PLSOP_ADVANCE_8")
      (footprint "eagle-import:SOP_ADVANCE_8")
      (fields
        (field (name "MF") "Toshiba")
        (field (name "MPN") "TPH1R204PL")
        (field (name "MF_1") "Toshiba")
        (field (name "MPN_1") "TPH2R506PL,L1Q")
      )
      (libsource (lib "eagle-import") (part "TPH1R204PLSOP_ADVANCE_8"))
    )
    (comp (ref "Q6")
      (value "TPH1R204PLSOP_ADVANCE_8")
      (footprint "eagle-import:SOP_ADVANCE_8")
      (fields
        (field (name "MF") "Toshiba")
        (field (name "MPN") "TPH1R204PL")
        (field (name "MF_1") "Toshiba")
        (field (name "MPN_1") "TPH2R506PL,L1Q")
      )
      (libsource (lib "eagle-import") (part "TPH1R204PLSOP_ADVANCE_8"))
    )
    (comp (ref "R1")
      (value "560")
      (footprint "eagle-import:R0402")
      (fields (field (name "HOUSEPART") "1") (field (name "MPN") "MF-RES-0402-560"))
      (libsource (lib "eagle-import") (part "RESISTOR_0402"))
    )
    (comp (ref "R2")
      (value "560")
      (footprint "eagle-import:R0402")
      (fields (field (name "HOUSEPART") "1") (field (name "MPN") "MF-RES-0402-560"))
      (libsource (lib "eagle-import") (part "RESISTOR_0402"))
    )
    (comp (ref "R3")
      (value "2k")
      (footprint "eagle-import:R0402")
      (fields (field (name "HOUSEPART") "YES") (field (name "MPN") "MF-RES-0402-2K"))
      (libsource (lib "eagle-import") (part "RESISTOR_0402"))
    )
    (comp (ref "R4")
      (value "2k")
      (footprint "eagle-import:R0402")
      (fields (field (name "HOUSEPART") "YES") (field (name "MPN") "MF-RES-0402-2K"))
      (libsource (lib "eagle-import") (part "RESISTOR_0402"))
    )
    (comp (ref "R5")
      (value "100k 1%")
      (footprint "eagle-import:R0402")
      (fields (field (name "MF") "Yageo") (field (name "MPN") "RC0402FR-07100KL"))
      (libsource (lib "eagle-import") (part "RESISTOR_0402"))
    )
    (comp (ref "R6")
      (value "4.7k 1%")
      (footprint "eagle-import:R0402")
      (fields (field (name "MF") "Yageo") (field (name "MPN") "RC0402FR-074K7L"))
      (libsource (lib "eagle-import") (part "RESISTOR_0402"))
    )
    (comp (ref "R7")
      (value "10k 1%")
      (footprint "eagle-import:R0402")
      (fields (field (name "MF") "Yageo") (field (name "MPN") "RC0402FR-0710KL"))
      (libsource (lib "eagle-import") (part "RESISTOR_0402"))
    )
    (comp (ref "R8")
      (value "47k NTC")
      (footprint "eagle-import:R0402")
      (fields (field (name "MF") "Murata") (field (name "MPN") "NCP15WB473F03RC"))
      (libsource (lib "eagle-import") (part "RESISTOR_0402"))
    )
    (comp (ref "R9")
      (value "10k 1%")
      (footprint "eagle-import:R0402")
      (fields (field (name "MF") "Yageo") (field (name "MPN") "RC0402FR-0710KL"))
      (libsource (lib "eagle-import") (part "RESISTOR_0402"))
    )
    (comp (ref "R10")
      (value "DNP")
      (footprint "eagle-import:R0402")
      (fields (field (name "POPULATE") "0"))
      (libsource (lib "eagle-import") (part "RESISTOR_0402"))
    )
    (comp (ref "R13")
      (value "2k")
      (footprint "eagle-import:R0402")
      (fields (field (name "HOUSEPART") "YES") (field (name "MPN") "MF-RES-0402-2K"))
      (libsource (lib "eagle-import") (part "RESISTOR_0402"))
    )
    (comp (ref "R14")
      (value "2k")
      (footprint "eagle-import:R0402")
      (fields (field (name "HOUSEPART") "YES") (field (name "MPN") "MF-RES-0402-2K"))
      (libsource (lib "eagle-import") (part "RESISTOR_0402"))
    )
    (comp (ref "RA")
      (value "0.5mOhm 1% 2W")
      (footprint "eagle-import:M1206")
      (fields (field (name "MF") "Stackpole Electronics") (field (name "MPN") "HCS1206FTL500"))
      (libsource (lib "eagle-import") (part "R-US_M1206"))
    )
    (comp (ref "RB")
      (value "0.5mOhm 1% 2W")
      (footprint "eagle-import:M1206")
      (fields (field (name "MF") "Stackpole Electronics") (field (name "MPN") "HCS1206FTL500"))
      (libsource (lib "eagle-import") (part "R-US_M1206"))
    )
    (comp (ref "RC")
      (value "0.5mOhm 1% 2W")
      (footprint "eagle-import:M1206")
      (fields (field (name "MF") "Stackpole Electronics") (field (name "MPN") "HCS1206FTL500"))
      (libsource (lib "eagle-import") (part "R-US_M1206"))
    )
    (comp (ref "SH1")
      (value "SHORTT5")
      (footprint "eagle-import:SHORT_TOP-50")
      (libsource (lib "eagle-import") (part "SHORTT5"))
    )
    (comp (ref "SH2")
      (value "SHORTT5")
      (footprint "eagle-import:SHORT_TOP-50")
      (libsource (lib "eagle-import") (part "SHORTT5"))
    )
    (comp (ref "SH3")
      (value "SHORTT5")
      (footprint "eagle-import:SHORT_TOP-50")
      (libsource (lib "eagle-import") (part "SHORTT5"))
    )
    (comp (ref "SH4")
      (value "SHORTMEDIUM")
      (footprint "eagle-import:SHORT_TOP-MEDIUM")
      (libsource (lib "eagle-import") (part "SHORTMEDIUM"))
    )
    (comp (ref "SWD")
      (value "JST-ZH6")
      (footprint "eagle-import:JST_S6B-ZR-SM4A-TF(LF)(SN)")
      (fields (field (name "MF") "JST") (field (name "MPN") "S6B-ZR-SM4A-TF(LF)(SN)"))
      (libsource (lib "eagle-import") (part "JST-ZH6"))
    )
    (comp (ref "TEMP1")
      (value "PAD24AWG_PAD")
      (footprint "eagle-import:24AWG_PAD")
      (libsource (lib "eagle-import") (part "PAD24AWG_PAD"))
    )
    (comp (ref "TEMP2")
      (value "PAD24AWG_PAD")
      (footprint "eagle-import:24AWG_PAD")
      (libsource (lib "eagle-import") (part "PAD24AWG_PAD"))
    )
    (comp (ref "U1")
      (value "STM32G474CEU6")
      (footprint "eagle-import:QFN50P700X700X60-49N")
      (fields (field (name "MOUSER_PART_NUMBER") "511-STM32G474CEU6"))
      (libsource (lib "eagle-import") (part "STM32G474CEU6"))
    )
    (comp (ref "U2")
      (value "TCAN334GSOT23")
      (footprint "eagle-import:SOT23-8")
      (fields (field (name "MF") "TI") (field (name "MPN") "TCAN334GDCNT"))
      (libsource (lib "eagle-import") (part "TCAN334GSOT23"))
    )
    (comp (ref "U3")
      (value "AS5147")
      (footprint "eagle-import:TSSOP14")
      (fields (field (name "MF") "AMS") (field (name "MPN") "AS5047P-ATSM"))
      (libsource (lib "eagle-import") (part "AS5147"))
    )
    (comp (ref "U4")
      (value "MAX15062AATA+T")
      (footprint "eagle-import:21-0487A_MXM")
      (fields (field (name "COPYRIGHT") "Copyright (C) 2018 Accelerated Designs. All rights reserved"))
      (libsource (lib "eagle-import") (part "MAX15062AATA+T"))
    )
    (comp (ref "U5")
      (value "DRV8353S")
      (footprint "eagle-import:WQFN-40")
      (fields (field (name "MF") "TI") (field (name "MPN") "DRV8353FSRTAR"))
      (libsource (lib "eagle-import") (part "DRV8353S"))
    )
  )
  (nets
    (net (code "1") (name "+3V3") (class "Default")
      (node (ref "ABS") (pin "1") (pinfunction "1_1") (pintype "passive"))
      (node (ref "C1") (pin "P$1") (pinfunction "P$1_P$1") (pintype "passive"))
      (node (ref "C10") (pin "P$1") (pinfunction "P$1_P$1") (pintype "passive"))
      (node (ref "C11") (pin "P$1") (pinfunction "P$1_P$1") (pintype "passive"))
      (node (ref "C12") (pin "P$1") (pinfunction "P$1_P$1") (pintype "passive"))
      (node (ref "C18") (pin "P$2") (pinfunction "P$2_P$2") (pintype "passive"))
      (node (ref "C2") (pin "P$1") (pinfunction "P$1_P$1") (pintype "passive"))
      (node (ref "C21") (pin "P$1") (pinfunction "P$1_P$1") (pintype "passive"))
      (node (ref "C4") (pin "P$1") (pinfunction "P$1_P$1") (pintype "passive"))
      (node (ref "C5") (pin "P$1") (pinfunction "P$1_P$1") (pintype "passive"))
      (node (ref "C56") (pin "P$1") (pinfunction "P$1_P$1") (pintype "passive"))
      (node (ref "C6") (pin "P$1") (pinfunction "P$1_P$1") (pintype "passive"))
      (node (ref "C7") (pin "P$2") (pinfunction "P$2_P$2") (pintype "passive"))
      (node (ref "C8") (pin "P$1") (pinfunction "P$1_P$1") (pintype "passive"))
      (node (ref "C9") (pin "P$1") (pinfunction "P$1_P$1") (pintype "passive"))
      (node (ref "D33") (pin "P$1") (pinfunction "P$1_P$1") (pintype "bidirectional"))
      (node (ref "ENC") (pin "1") (pinfunction "1_1") (pintype "passive"))
      (node (ref "L1") (pin "1") (pinfunction "1_1") (pintype "passive"))
      (node (ref "R1") (pin "P$1") (pinfunction "P$1_P$1") (pintype "passive"))
      (node (ref "R13") (pin "P$1") (pinfunction "P$1_P$1") (pintype "passive"))
      (node (ref "R14") (pin "P$1") (pinfunction "P$1_P$1") (pintype "passive"))
      (node (ref "R2") (pin "P$1") (pinfunction "P$1_P$1") (pintype "passive"))
      (node (ref "R3") (pin "P$1") (pinfunction "P$1_P$1") (pintype "passive"))
      (node (ref "R4") (pin "P$1") (pinfunction "P$1_P$1") (pintype "passive"))
      (node (ref "R8") (pin "P$1") (pinfunction "P$1_P$1") (pintype "passive"))
      (node (ref "SWD") (pin "6") (pinfunction "6_6") (pintype "passive"))
      (node (ref "TEMP1") (pin "P$1") (pinfunction "P$1_P$1") (pintype "bidirectional"))
      (node (ref "U1") (pin "1") (pinfunction "VBAT_1") (pintype "bidirectional"))
      (node (ref "U1") (pin "20") (pinfunction "VREF+_20") (pintype "bidirectional"))
      (node (ref "U1") (pin "21") (pinfunction "VDDA_21") (pintype "bidirectional"))
      (node (ref "U1") (pin "23") (pinfunction "VDD_1_23") (pintype "bidirectional"))
      (node (ref "U1") (pin "35") (pinfunction "VDD_2_35") (pintype "bidirectional"))
      (node (ref "U1") (pin "48") (pinfunction "VDD_3_48") (pintype "bidirectional"))
      (node (ref "U2") (pin "3") (pinfunction "VCC_3") (pintype "power_in"))
      (node (ref "U3") (pin "12") (pinfunction "VDD3V_12") (pintype "bidirectional"))
      (node (ref "U4") (pin "4") (pinfunction "FB/VOUT_4") (pintype "bidirectional"))
      (node (ref "U5") (pin "24") (pinfunction "VREF_24") (pintype "bidirectional"))
    )
    (net (code "2") (name "/AS5047_A") (class "Default")
      (node (ref "U1") (pin "43") (pinfunction "PB5_43") (pintype "bidirectional"))
      (node (ref "U3") (pin "7") (pinfunction "A_7") (pintype "bidirectional"))
    )
    (net (code "3") (name "/AS5047_B") (class "Default")
      (node (ref "U1") (pin "42") (pinfunction "PB4_42") (pintype "bidirectional"))
      (node (ref "U3") (pin "6") (pinfunction "B_6") (pintype "bidirectional"))
    )
    (net (code "4") (name "/AS5047_CS") (class "Default")
      (node (ref "U1") (pin "24") (pinfunction "PB11_24") (pintype "bidirectional"))
      (node (ref "U3") (pin "1") (pinfunction "CS/_1") (pintype "bidirectional"))
    )
    (net (code "5") (name "/AS5047_MISO") (class "Default")
      (node (ref "ENC") (pin "5") (pinfunction "5_5") (pintype "passive"))
      (node (ref "U1") (pin "27") (pinfunction "PB14_27") (pintype "bidirectional"))
      (node (ref "U3") (pin "3") (pinfunction "MISO_3") (pintype "bidirectional"))
    )
    (net (code "6") (name "/AS5047_MOSI") (class "Default")
      (node (ref "ENC") (pin "6") (pinfunction "6_6") (pintype "passive"))
      (node (ref "U1") (pin "28") (pinfunction "PB15_28") (pintype "bidirectional"))
      (node (ref "U3") (pin "4") (pinfunction "MOSI_4") (pintype "bidirectional"))
    )
    (net (code "7") (name "/AS5047_SCK") (class "Default")
      (node (ref "ENC") (pin "4") (pinfunction "4_4") (pintype "passive"))
      (node (ref "U1") (pin "26") (pinfunction "PB13_26") (pintype "bidirectional"))
      (node (ref "U3") (pin "2") (pinfunction "CLK_2") (pintype "bidirectional"))
    )
    (net (code "8") (name "/CAN2_N") (class "Default")
      (node (ref "L2") (pin "P$2") (pinfunction "2_P$2") (pintype "passive"))
      (node (ref "U2") (pin "6") (pinfunction "CANL_6") (pintype "bidirectional"))
    )
    (net (code "9") (name "/CAN2_P") (class "Default")
      (node (ref "L3") (pin "P$2") (pinfunction "2_P$2") (pintype "passive"))
      (node (ref "U2") (pin "7") (pinfunction "CANH_7") (pintype "bidirectional"))
    )
    (net (code "10") (name "/CAN_N") (class "Default")
      (node (ref "CAN1") (pin "2") (pinfunction "2_2") (pintype "passive"))
      (node (ref "CAN2") (pin "2") (pinfunction "2_2") (pintype "passive"))
      (node (ref "D4") (pin "2") (pinfunction "2_2") (pintype "bidirectional"))
      (node (ref "L2") (pin "P$1") (pinfunction "1_P$1") (pintype "passive"))
    )
    (net (code "11") (name "/CAN_P") (class "Default")
      (node (ref "CAN1") (pin "1") (pinfunction "1_1") (pintype "passive"))
      (node (ref "CAN2") (pin "1") (pinfunction "1_1") (pintype "passive"))
      (node (ref "D4") (pin "1") (pinfunction "1_1") (pintype "bidirectional"))
      (node (ref "L3") (pin "P$1") (pinfunction "1_P$1") (pintype "passive"))
    )
    (net (code "12") (name "/CAN_RX") (class "Default")
      (node (ref "U1") (pin "33") (pinfunction "PA11_33") (pintype "bidirectional"))
      (node (ref "U2") (pin "4") (pinfunction "RXD_4") (pintype "output"))
    )
    (net (code "13") (name "/CAN_TX") (class "Default")
      (node (ref "U1") (pin "34") (pinfunction "PA12_34") (pintype "bidirectional"))
      (node (ref "U2") (pin "1") (pinfunction "TXD_1") (pintype "input"))
    )
    (net (code "14") (name "/CUR1") (class "Default")
      (node (ref "CUR1") (pin "P$1") (pinfunction "P$1_P$1") (pintype "bidirectional"))
      (node (ref "U1") (pin "17") (pinfunction "PB0_17") (pintype "bidirectional"))
      (node (ref "U5") (pin "23") (pinfunction "SOA_23") (pintype "bidirectional"))
    )
    (net (code "15") (name "/CUR2") (class "Default")
      (node (ref "CUR2") (pin "P$1") (pinfunction "P$1_P$1") (pintype "bidirectional"))
      (node (ref "U1") (pin "18") (pinfunction "PB1_18") (pintype "bidirectional"))
      (node (ref "U5") (pin "22") (pinfunction "SOB_22") (pintype "bidirectional"))
    )
    (net (code "16") (name "/CUR3") (class "Default")
      (node (ref "CUR3") (pin "P$1") (pinfunction "P$1_P$1") (pintype "bidirectional"))
      (node (ref "U1") (pin "19") (pinfunction "PB2_19") (pintype "bidirectional"))
      (node (ref "U5") (pin "21") (pinfunction "SOC_21") (pintype "bidirectional"))
    )
    (net (code "17") (name "/DAC") (class "Default")
      (node (ref "DAC") (pin "P$1") (pinfunction "P$1_P$1") (pintype "bidirectional"))
      (node (ref "U1") (pin "12") (pinfunction "PA4_12") (pintype "bidirectional"))
    )
    (net (code "18") (name "/DEBUG1") (class "Default")
      (node (ref "DBG1") (pin "P$1") (pinfunction "P$1_P$1") (pintype "bidirectional"))
      (node (ref "U1") (pin "3") (pinfunction "PC14-OSC32_IN_3") (pintype "bidirectional"))
    )
    (net (code "19") (name "/DEBUG2") (class "Default")
      (node (ref "DBG2") (pin "P$1") (pinfunction "P$1_P$1") (pintype "bidirectional"))
      (node (ref "U1") (pin "4") (pinfunction "PC15-OSC32_OUT_4") (pintype "bidirectional"))
    )
    (net (code "20") (name "/DEBUG_RX") (class "Default")
      (node (ref "DTR") (pin "P$1") (pinfunction "P$1_P$1") (pintype "bidirectional"))
      (node (ref "U1") (pin "40") (pinfunction "PC11_40") (pintype "bidirectional"))
    )
    (net (code "21") (name "/DEBUG_TX") (class "Default")
      (node (ref "DTX") (pin "P$1") (pinfunction "P$1_P$1") (pintype "bidirectional"))
      (node (ref "U1") (pin "39") (pinfunction "PC10_39") (pintype "bidirectional"))
    )
    (net (code "22") (name "/DRV8323_CS") (class "Default")
      (node (ref "DRV_CS") (pin "P$1") (pinfunction "P$1_P$1") (pintype "bidirectional"))
      (node (ref "U1") (pin "16") (pinfunction "PC4_16") (pintype "bidirectional"))
      (node (ref "U5") (pin "30") (pinfunction "CS_30") (pintype "bidirectional"))
    )
    (net (code "23") (name "/DRV8323_MISO") (class "Default")
      (node (ref "DRV_MISO") (pin "P$1") (pinfunction "P$1_P$1") (pintype "bidirectional"))
      (node (ref "R13") (pin "P$2") (pinfunction "P$2_P$2") (pintype "passive"))
      (node (ref "U1") (pin "14") (pinfunction "PA6_14") (pintype "bidirectional"))
      (node (ref "U5") (pin "27") (pinfunction "MISO_27") (pintype "bidirectional"))
    )
    (net (code "24") (name "/DRV8323_MOSI") (class "Default")
      (node (ref "DRV_MOSI") (pin "P$1") (pinfunction "P$1_P$1") (pintype "bidirectional"))
      (node (ref "U1") (pin "15") (pinfunction "PA7_15") (pintype "bidirectional"))
      (node (ref "U5") (pin "28") (pinfunction "MOSI_28") (pintype "bidirectional"))
    )
    (net (code "25") (name "/DRV8323_SCLK") (class "Default")
      (node (ref "DRV_SCK") (pin "P$1") (pinfunction "P$1_P$1") (pintype "bidirectional"))
      (node (ref "U1") (pin "13") (pinfunction "PA5_13") (pintype "bidirectional"))
      (node (ref "U5") (pin "29") (pinfunction "SCLK_29") (pintype "bidirectional"))
    )
    (net (code "26") (name "/GHA") (class "Default")
      (node (ref "Q1") (pin "4") (pinfunction "G_4") (pintype "passive"))
      (node (ref "U5") (pin "6") (pinfunction "GHA_6") (pintype "bidirectional"))
    )
    (net (code "27") (name "/GHB") (class "Default")
      (node (ref "Q3") (pin "4") (pinfunction "G_4") (pintype "passive"))
      (node (ref "U5") (pin "15") (pinfunction "GHB_15") (pintype "bidirectional"))
    )
    (net (code "28") (name "/GHC") (class "Default")
      (node (ref "Q5") (pin "4") (pinfunction "G_4") (pintype "passive"))
      (node (ref "U5") (pin "16") (pinfunction "GHC_16") (pintype "bidirectional"))
    )
    (net (code "29") (name "/GLA") (class "Default")
      (node (ref "Q2") (pin "4") (pinfunction "G_4") (pintype "passive"))
      (node (ref "U5") (pin "8") (pinfunction "GLA_8") (pintype "bidirectional"))
    )
    (net (code "30") (name "/GLB") (class "Default")
      (node (ref "Q4") (pin "4") (pinfunction "G_4") (pintype "passive"))
      (node (ref "U5") (pin "13") (pinfunction "GLB_13") (pintype "bidirectional"))
    )
    (net (code "31") (name "/GLC") (class "Default")
      (node (ref "Q6") (pin "4") (pinfunction "G_4") (pintype "passive"))
      (node (ref "U5") (pin "18") (pinfunction "GLC_18") (pintype "bidirectional"))
    )
    (net (code "32") (name "/I2C_ABS_SCL") (class "Default")
      (node (ref "ABS") (pin "2") (pinfunction "2_2") (pintype "passive"))
      (node (ref "R4") (pin "P$2") (pinfunction "P$2_P$2") (pintype "passive"))
      (node (ref "U1") (pin "46") (pinfunction "PB8-BOOT0_46") (pintype "bidirectional"))
    )
    (net (code "33") (name "/I2C_ABS_SDA") (class "Default")
      (node (ref "ABS") (pin "3") (pinfunction "3_3") (pintype "passive"))
      (node (ref "R3") (pin "P$2") (pinfunction "P$2_P$2") (pintype "passive"))
      (node (ref "U1") (pin "47") (pinfunction "PB9_47") (pintype "bidirectional"))
    )
    (net (code "34") (name "/LED1") (class "Default")
      (node (ref "D3") (pin "CATHODE") (pinfunction "CATHODE_CATHODE") (pintype "power_in"))
      (node (ref "U1") (pin "5") (pinfunction "PF0-OSC_IN_5") (pintype "bidirectional"))
    )
    (net (code "35") (name "/LED2") (class "Default")
      (node (ref "D2") (pin "CATHODE") (pinfunction "CATHODE_CATHODE") (pintype "power_in"))
      (node (ref "U1") (pin "6") (pinfunction "PF1-OSC_OUT_6") (pintype "bidirectional"))
    )
    (net (code "36") (name "/MOTOR1") (class "Default")
      (node (ref "MOT1") (pin "P$1") (pinfunction "P$1_P$1") (pintype "bidirectional"))
      (node (ref "U1") (pin "8") (pinfunction "PA0_8") (pintype "bidirectional"))
      (node (ref "U5") (pin "32") (pinfunction "INHA_32") (pintype "bidirectional"))
    )
    (net (code "37") (name "/MOTOR2") (class "Default")
      (node (ref "MOT2") (pin "P$1") (pinfunction "P$1_P$1") (pintype "bidirectional"))
      (node (ref "U1") (pin "9") (pinfunction "PA1_9") (pintype "bidirectional"))
      (node (ref "U5") (pin "34") (pinfunction "INHB_34") (pintype "bidirectional"))
    )
    (net (code "38") (name "/MOTOR3") (class "Default")
      (node (ref "MOT3") (pin "P$1") (pinfunction "P$1_P$1") (pintype "bidirectional"))
      (node (ref "U1") (pin "10") (pinfunction "PA2_10") (pintype "bidirectional"))
      (node (ref "U5") (pin "36") (pinfunction "INHC_36") (pintype "bidirectional"))
    )
    (net (code "39") (name "/MOTOR_ENABLE") (class "Default")
      (node (ref "U1") (pin "11") (pinfunction "PA3_11") (pintype "bidirectional"))
      (node (ref "U5") (pin "31") (pinfunction "ENABLE_31") (pintype "bidirectional"))
    )
    (net (code "40") (name "/MOTOR_FAULT") (class "Default")
      (node (ref "R14") (pin "P$2") (pinfunction "P$2_P$2") (pintype "passive"))
      (node (ref "U1") (pin "44") (pinfunction "PB6_44") (pintype "bidirectional"))
      (node (ref "U5") (pin "26") (pinfunction "FAULT_26") (pintype "bidirectional"))
    )
    (net (code "41") (name "/MOTOR_HIZ") (class "Default")
      (node (ref "U1") (pin "45") (pinfunction "PB7_45") (pintype "bidirectional"))
      (node (ref "U5") (pin "33") (pinfunction "INLA_33") (pintype "bidirectional"))
      (node (ref "U5") (pin "35") (pinfunction "INLB_35") (pintype "bidirectional"))
      (node (ref "U5") (pin "37") (pinfunction "INLC_37") (pintype "bidirectional"))
    )
    (net (code "42") (name "/NRST") (class "Default")
      (node (ref "C3") (pin "P$1") (pinfunction "P$1_P$1") (pintype "passive"))
      (node (ref "SWD") (pin "2") (pinfunction "2_2") (pintype "passive"))
      (node (ref "U1") (pin "7") (pinfunction "PG10-NRST_7") (pintype "bidirectional"))
    )
    (net (code "43") (name "/SECONDARY_ENC_CS") (class "Default")
      (node (ref "ENC") (pin "2") (pinfunction "2_2") (pintype "passive"))
      (node (ref "U1") (pin "2") (pinfunction "PC13_2") (pintype "bidirectional"))
    )
    (net (code "44") (name "/SHA") (class "Default")
      (node (ref "A") (pin "1") (pinfunction "P$1_1") (pintype "bidirectional"))
      (node (ref "DA") (pin "P$1") (pinfunction "P$1_P$1") (pintype "bidirectional"))
      (node (ref "Q1") (pin "1") (pinfunction "S_1") (pintype "passive"))
      (node (ref "Q1") (pin "2") (pinfunction "S_2") (pintype "passive"))
      (node (ref "Q1") (pin "3") (pinfunction "S_3") (pintype "passive"))
      (node (ref "Q2") (pin "5") (pinfunction "D_5") (pintype "passive"))
      (node (ref "Q2") (pin "6") (pinfunction "D_6") (pintype "passive"))
      (node (ref "Q2") (pin "7") (pinfunction "D_7") (pintype "passive"))
      (node (ref "Q2") (pin "8") (pinfunction "D_8") (pintype "passive"))
      (node (ref "Q2") (pin "PAD") (pinfunction "D_PAD") (pintype "passive"))
      (node (ref "U5") (pin "7") (pinfunction "SHA_7") (pintype "bidirectional"))
    )
    (net (code "45") (name "/SHB") (class "Default")
      (node (ref "B") (pin "1") (pinfunction "P$1_1") (pintype "bidirectional"))
      (node (ref "DB") (pin "P$1") (pinfunction "P$1_P$1") (pintype "bidirectional"))
      (node (ref "Q3") (pin "1") (pinfunction "S_1") (pintype "passive"))
      (node (ref "Q3") (pin "2") (pinfunction "S_2") (pintype "passive"))
      (node (ref "Q3") (pin "3") (pinfunction "S_3") (pintype "passive"))
      (node (ref "Q4") (pin "5") (pinfunction "D_5") (pintype "passive"))
      (node (ref "Q4") (pin "6") (pinfunction "D_6") (pintype "passive"))
      (node (ref "Q4") (pin "7") (pinfunction "D_7") (pintype "passive"))
      (node (ref "Q4") (pin "8") (pinfunction "D_8") (pintype "passive"))
      (node (ref "Q4") (pin "PAD") (pinfunction "D_PAD") (pintype "passive"))
      (node (ref "U5") (pin "14") (pinfunction "SHB_14") (pintype "bidirectional"))
    )
    (net (code "46") (name "/SHC") (class "Default")
      (node (ref "C") (pin "1") (pinfunction "P$1_1") (pintype "bidirectional"))
      (node (ref "DC") (pin "P$1") (pinfunction "P$1_P$1") (pintype "bidirectional"))
      (node (ref "Q5") (pin "1") (pinfunction "S_1") (pintype "passive"))
      (node (ref "Q5") (pin "2") (pinfunction "S_2") (pintype "passive"))
      (node (ref "Q5") (pin "3") (pinfunction "S_3") (pintype "passive"))
      (node (ref "Q6") (pin "5") (pinfunction "D_5") (pintype "passive"))
      (node (ref "Q6") (pin "6") (pinfunction "D_6") (pintype "passive"))
      (node (ref "Q6") (pin "7") (pinfunction "D_7") (pintype "passive"))
      (node (ref "Q6") (pin "8") (pinfunction "D_8") (pintype "passive"))
      (node (ref "Q6") (pin "PAD") (pinfunction "D_PAD") (pintype "passive"))
      (node (ref "U5") (pin "17") (pinfunction "SHC_17") (pintype "bidirectional"))
    )
    (net (code "47") (name "/SNA") (class "Default")
      (node (ref "SH1") (pin "1") (pinfunction "P$1_1") (pintype "bidirectional"))
      (node (ref "U5") (pin "10") (pinfunction "SNA_10") (pintype "bidirectional"))
    )
    (net (code "48") (name "/SNB") (class "Default")
      (node (ref "SH2") (pin "1") (pinfunction "P$1_1") (pintype "bidirectional"))
      (node (ref "U5") (pin "11") (pinfunction "SNB_11") (pintype "bidirectional"))
    )
    (net (code "49") (name "/SNC") (class "Default")
      (node (ref "SH3") (pin "1") (pinfunction "P$1_1") (pintype "bidirectional"))
      (node (ref "U5") (pin "20") (pinfunction "SNC_20") (pintype "bidirectional"))
    )
    (net (code "50") (name "/SPA") (class "Default")
      (node (ref "Q2") (pin "1") (pinfunction "S_1") (pintype "passive"))
      (node (ref "Q2") (pin "2") (pinfunction "S_2") (pintype "passive"))
      (node (ref "Q2") (pin "3") (pinfunction "S_3") (pintype "passive"))
      (node (ref "RA") (pin "2") (pinfunction "2_2") (pintype "passive"))
      (node (ref "U5") (pin "9") (pinfunction "SPA_9") (pintype "bidirectional"))
    )
    (net (code "51") (name "/SPB") (class "Default")
      (node (ref "Q4") (pin "1") (pinfunction "S_1") (pintype "passive"))
      (node (ref "Q4") (pin "2") (pinfunction "S_2") (pintype "passive"))
      (node (ref "Q4") (pin "3") (pinfunction "S_3") (pintype "passive"))
      (node (ref "RB") (pin "2") (pinfunction "2_2") (pintype "passive"))
      (node (ref "U5") (pin "12") (pinfunction "SPB_12") (pintype "bidirectional"))
    )
    (net (code "52") (name "/SPC") (class "Default")
      (node (ref "Q6") (pin "1") (pinfunction "S_1") (pintype "passive"))
      (node (ref "Q6") (pin "2") (pinfunction "S_2") (pintype "passive"))
      (node (ref "Q6") (pin "3") (pinfunction "S_3") (pintype "passive"))
      (node (ref "RC") (pin "2") (pinfunction "2_2") (pintype "passive"))
      (node (ref "U5") (pin "19") (pinfunction "SPC_19") (pintype "bidirectional"))
    )
    (net (code "53") (name "/SWCLK") (class "Default")
      (node (ref "SWD") (pin "5") (pinfunction "5_5") (pintype "passive"))
      (node (ref "U1") (pin "37") (pinfunction "PA14_37") (pintype "bidirectional"))
    )
    (net (code "54") (name "/SWDIO") (class "Default")
      (node (ref "SWD") (pin "3") (pinfunction "3_3") (pintype "passive"))
      (node (ref "U1") (pin "36") (pinfunction "PA13_36") (pintype "bidirectional"))
    )
    (net (code "55") (name "/VBAT_SENSE") (class "Default")
      (node (ref "R5") (pin "P$1") (pinfunction "P$1_P$1") (pintype "passive"))
      (node (ref "R6") (pin "P$2") (pinfunction "P$2_P$2") (pintype "passive"))
      (node (ref "U1") (pin "25") (pinfunction "PB12_25") (pintype "bidirectional"))
    )
    (net (code "56") (name "/VSW") (class "Default")
      (node (ref "L1") (pin "2") (pinfunction "2_2") (pintype "passive"))
      (node (ref "U4") (pin "8") (pinfunction "LX_8") (pintype "passive"))
    )
    (net (code "57") (name "/VTEMP_FET") (class "Default")
      (node (ref "C13") (pin "P$1") (pinfunction "P$1_P$1") (pintype "passive"))
      (node (ref "R8") (pin "P$2") (pinfunction "P$2_P$2") (pintype "passive"))
      (node (ref "R9") (pin "P$1") (pinfunction "P$1_P$1") (pintype "passive"))
      (node (ref "U1") (pin "31") (pinfunction "PA9_31") (pintype "bidirectional"))
    )
    (net (code "58") (name "/VTEMP_MOT") (class "Default")
      (node (ref "R7") (pin "P$1") (pinfunction "P$1_P$1") (pintype "passive"))
      (node (ref "TEMP2") (pin "P$1") (pinfunction "P$1_P$1") (pintype "bidirectional"))
      (node (ref "U1") (pin "30") (pinfunction "PA8_30") (pintype "bidirectional"))
    )
    (net (code "59") (name "GND") (class "Default")
      (node (ref "ABS") (pin "4") (pinfunction "4_4") (pintype "passive"))
      (node (ref "C1") (pin "P$2") (pinfunction "P$2_P$2") (pintype "passive"))
      (node (ref "C10") (pin "P$2") (pinfunction "P$2_P$2") (pintype "passive"))
      (node (ref "C11") (pin "P$2") (pinfunction "P$2_P$2") (pintype "passive"))
      (node (ref "C12") (pin "P$2") (pinfunction "P$2_P$2") (pintype "passive"))
      (node (ref "C13") (pin "P$2") (pinfunction "P$2_P$2") (pintype "passive"))
      (node (ref "C18") (pin "P$1") (pinfunction "P$1_P$1") (pintype "passive"))
      (node (ref "C2") (pin "P$2") (pinfunction "P$2_P$2") (pintype "passive"))
      (node (ref "C20") (pin "P$2") (pinfunction "P$2_P$2") (pintype "passive"))
      (node (ref "C21") (pin "P$2") (pinfunction "P$2_P$2") (pintype "passive"))
      (node (ref "C3") (pin "P$2") (pinfunction "P$2_P$2") (pintype "passive"))
      (node (ref "C4") (pin "P$2") (pinfunction "P$2_P$2") (pintype "passive"))
      (node (ref "C5") (pin "P$2") (pinfunction "P$2_P$2") (pintype "passive"))
      (node (ref "C56") (pin "P$2") (pinfunction "P$2_P$2") (pintype "passive"))
      (node (ref "C6") (pin "P$2") (pinfunction "P$2_P$2") (pintype "passive"))
      (node (ref "C7") (pin "P$1") (pinfunction "P$1_P$1") (pintype "passive"))
      (node (ref "C8") (pin "P$2") (pinfunction "P$2_P$2") (pintype "passive"))
      (node (ref "C9") (pin "P$2") (pinfunction "P$2_P$2") (pintype "passive"))
      (node (ref "CAN1") (pin "3") (pinfunction "3_3") (pintype "passive"))
      (node (ref "CAN2") (pin "3") (pinfunction "3_3") (pintype "passive"))
      (node (ref "D4") (pin "3") (pinfunction "3_3") (pintype "bidirectional"))
      (node (ref "DG1") (pin "P$1") (pinfunction "P$1_P$1") (pintype "bidirectional"))
      (node (ref "DG2") (pin "P$1") (pinfunction "P$1_P$1") (pintype "bidirectional"))
      (node (ref "ENC") (pin "3") (pinfunction "3_3") (pintype "passive"))
      (node (ref "R6") (pin "P$1") (pinfunction "P$1_P$1") (pintype "passive"))
      (node (ref "R7") (pin "P$2") (pinfunction "P$2_P$2") (pintype "passive"))
      (node (ref "R9") (pin "P$2") (pinfunction "P$2_P$2") (pintype "passive"))
      (node (ref "SH4") (pin "2") (pinfunction "P$2_2") (pintype "bidirectional"))
      (node (ref "SWD") (pin "4") (pinfunction "4_4") (pintype "passive"))
      (node (ref "U1") (pin "29") (pinfunction "PC6_29") (pintype "bidirectional"))
      (node (ref "U1") (pin "38") (pinfunction "PA15_38") (pintype "bidirectional"))
      (node (ref "U1") (pin "49") (pinfunction "THERMALPAD_49") (pintype "bidirectional"))
      (node (ref "U2") (pin "2") (pinfunction "GND_2") (pintype "power_in"))
      (node (ref "U2") (pin "5") (pinfunction "SHDN_5") (pintype "input"))
      (node (ref "U2") (pin "8") (pinfunction "STB_8") (pintype "input"))
      (node (ref "U3") (pin "13") (pinfunction "GND_13") (pintype "bidirectional"))
      (node (ref "U3") (pin "5") (pinfunction "TEST_5") (pintype "bidirectional"))
      (node (ref "U4") (pin "7") (pinfunction "GND_7") (pintype "power_in"))
      (node (ref "U5") (pin "25") (pinfunction "AGND_25") (pintype "bidirectional"))
    )
    (net (code "60") (name "Net-(C55-PadP$1)") (class "Default")
      (node (ref "C55") (pin "P$1") (pinfunction "P$1_P$1") (pintype "passive"))
      (node (ref "M3") (pin "P$1") (pinfunction "P$1_P$1") (pintype "bidirectional"))
      (node (ref "R10") (pin "P$1") (pinfunction "P$1_P$1") (pintype "passive"))
    )
    (net (code "61") (name "Net-(D2-PadANODE)") (class "Default")
      (node (ref "D2") (pin "ANODE") (pinfunction "ANODE_ANODE") (pintype "power_in"))
      (node (ref "R2") (pin "P$2") (pinfunction "P$2_P$2") (pintype "passive"))
    )
    (net (code "62") (name "Net-(D3-PadANODE)") (class "Default")
      (node (ref "D3") (pin "ANODE") (pinfunction "ANODE_ANODE") (pintype "power_in"))
      (node (ref "R1") (pin "P$2") (pinfunction "P$2_P$2") (pintype "passive"))
    )
    (net (code "63") (name "Net-(U4-VCC)") (class "Default")
      (node (ref "C20") (pin "P$1") (pinfunction "P$1_P$1") (pintype "passive"))
      (node (ref "U4") (pin "3") (pinfunction "VCC_3") (pintype "power_in"))
    )
    (net (code "64") (name "Net-(U5-CPH)") (class "Default")
      (node (ref "C16") (pin "P$1") (pinfunction "P$1_P$1") (pintype "passive"))
      (node (ref "U5") (pin "2") (pinfunction "CPH_2") (pintype "bidirectional"))
    )
    (net (code "65") (name "Net-(U5-CPL)") (class "Default")
      (node (ref "C16") (pin "P$2") (pinfunction "P$2_P$2") (pintype "passive"))
      (node (ref "U5") (pin "1") (pinfunction "CPL_1") (pintype "bidirectional"))
    )
    (net (code "66") (name "Net-(U5-DVDD)") (class "Default")
      (node (ref "C17") (pin "P$2") (pinfunction "P$2_P$2") (pintype "passive"))
      (node (ref "U5") (pin "38") (pinfunction "DVDD_38") (pintype "bidirectional"))
    )
    (net (code "67") (name "Net-(U5-VCP)") (class "Default")
      (node (ref "C15") (pin "P$2") (pinfunction "P$2_P$2") (pintype "passive"))
      (node (ref "U5") (pin "5") (pinfunction "VCP_5") (pintype "bidirectional"))
    )
    (net (code "68") (name "Net-(U5-VGLS)") (class "Default")
      (node (ref "C38") (pin "P$2") (pinfunction "P$2_P$2") (pintype "passive"))
      (node (ref "U5") (pin "40") (pinfunction "VGLS_40") (pintype "bidirectional"))
    )
    (net (code "69") (name "V+") (class "Default")
      (node (ref "C14") (pin "P$1") (pinfunction "P$1_P$1") (pintype "passive"))
      (node (ref "C15") (pin "P$1") (pinfunction "P$1_P$1") (pintype "passive"))
      (node (ref "C19") (pin "P$1") (pinfunction "P$1_P$1") (pintype "passive"))
      (node (ref "C22") (pin "P$1") (pinfunction "P$1_P$1") (pintype "passive"))
      (node (ref "C23") (pin "P$1") (pinfunction "P$1_P$1") (pintype "passive"))
      (node (ref "C24") (pin "P$1") (pinfunction "P$1_P$1") (pintype "passive"))
      (node (ref "C25") (pin "P$1") (pinfunction "P$1_P$1") (pintype "passive"))
      (node (ref "C26") (pin "P$1") (pinfunction "P$1_P$1") (pintype "passive"))
      (node (ref "C27") (pin "P$1") (pinfunction "P$1_P$1") (pintype "passive"))
      (node (ref "C28") (pin "P$1") (pinfunction "P$1_P$1") (pintype "passive"))
      (node (ref "C29") (pin "P$1") (pinfunction "P$1_P$1") (pintype "passive"))
      (node (ref "C30") (pin "P$1") (pinfunction "P$1_P$1") (pintype "passive"))
      (node (ref "C31") (pin "P$1") (pinfunction "P$1_P$1") (pintype "passive"))
      (node (ref "C32") (pin "P$1") (pinfunction "P$1_P$1") (pintype "passive"))
      (node (ref "C33") (pin "P$1") (pinfunction "P$1_P$1") (pintype "passive"))
      (node (ref "C34") (pin "P$1") (pinfunction "P$1_P$1") (pintype "passive"))
      (node (ref "C35") (pin "P$1") (pinfunction "P$1_P$1") (pintype "passive"))
      (node (ref "C36") (pin "P$1") (pinfunction "P$1_P$1") (pintype "passive"))
      (node (ref "C37") (pin "P$1") (pinfunction "P$1_P$1") (pintype "passive"))
      (node (ref "C39") (pin "P$1") (pinfunction "P$1_P$1") (pintype "passive"))
      (node (ref "C40") (pin "P$1") (pinfunction "P$1_P$1") (pintype "passive"))
      (node (ref "C41") (pin "P$1") (pinfunction "P$1_P$1") (pintype "passive"))
      (node (ref "C42") (pin "P$1") (pinfunction "P$1_P$1") (pintype "passive"))
      (node (ref "C43") (pin "P$1") (pinfunction "P$1_P$1") (pintype "passive"))
      (node (ref "C44") (pin "P$1") (pinfunction "P$1_P$1") (pintype "passive"))
      (node (ref "C45") (pin "P$1") (pinfunction "P$1_P$1") (pintype "passive"))
      (node (ref "C46") (pin "P$1") (pinfunction "P$1_P$1") (pintype "passive"))
      (node (ref "C47") (pin "P$1") (pinfunction "P$1_P$1") (pintype "passive"))
      (node (ref "C48") (pin "P$1") (pinfunction "P$1_P$1") (pintype "passive"))
      (node (ref "C49") (pin "P$1") (pinfunction "P$1_P$1") (pintype "passive"))
      (node (ref "C50") (pin "P$1") (pinfunction "P$1_P$1") (pintype "passive"))
      (node (ref "C51") (pin "P$1") (pinfunction "P$1_P$1") (pintype "passive"))
      (node (ref "C52") (pin "P$1") (pinfunction "P$1_P$1") (pintype "passive"))
      (node (ref "C53") (pin "P$1") (pinfunction "P$1_P$1") (pintype "passive"))
      (node (ref "C54") (pin "P$1") (pinfunction "P$1_P$1") (pintype "passive"))
      (node (ref "J1") (pin "1") (pinfunction "1_1") (pintype "passive"))
      (node (ref "J2") (pin "1") (pinfunction "1_1") (pintype "passive"))
      (node (ref "Q1") (pin "5") (pinfunction "D_5") (pintype "passive"))
      (node (ref "Q1") (pin "6") (pinfunction "D_6") (pintype "passive"))
      (node (ref "Q1") (pin "7") (pinfunction "D_7") (pintype "passive"))
      (node (ref "Q1") (pin "8") (pinfunction "D_8") (pintype "passive"))
      (node (ref "Q1") (pin "PAD") (pinfunction "D_PAD") (pintype "passive"))
      (node (ref "Q3") (pin "5") (pinfunction "D_5") (pintype "passive"))
      (node (ref "Q3") (pin "6") (pinfunction "D_6") (pintype "passive"))
      (node (ref "Q3") (pin "7") (pinfunction "D_7") (pintype "passive"))
      (node (ref "Q3") (pin "8") (pinfunction "D_8") (pintype "passive"))
      (node (ref "Q3") (pin "PAD") (pinfunction "D_PAD") (pintype "passive"))
      (node (ref "Q5") (pin "5") (pinfunction "D_5") (pintype "passive"))
      (node (ref "Q5") (pin "6") (pinfunction "D_6") (pintype "passive"))
      (node (ref "Q5") (pin "7") (pinfunction "D_7") (pintype "passive"))
      (node (ref "Q5") (pin "8") (pinfunction "D_8") (pintype "passive"))
      (node (ref "Q5") (pin "PAD") (pinfunction "D_PAD") (pintype "passive"))
      (node (ref "R5") (pin "P$2") (pinfunction "P$2_P$2") (pintype "passive"))
      (node (ref "U4") (pin "1") (pinfunction "VIN_1") (pintype "input"))
      (node (ref "U4") (pin "2") (pinfunction "EN/UVLO_2") (pintype "input"))
      (node (ref "U5") (pin "3") (pinfunction "VM_3") (pintype "bidirectional"))
      (node (ref "U5") (pin "4") (pinfunction "VDRAIN_4") (pintype "bidirectional"))
    )
    (net (code "70") (name "V-") (class "Default")
      (node (ref "C14") (pin "P$2") (pinfunction "P$2_P$2") (pintype "passive"))
      (node (ref "C17") (pin "P$1") (pinfunction "P$1_P$1") (pintype "passive"))
      (node (ref "C19") (pin "P$2") (pinfunction "P$2_P$2") (pintype "passive"))
      (node (ref "C22") (pin "P$2") (pinfunction "P$2_P$2") (pintype "passive"))
      (node (ref "C23") (pin "P$2") (pinfunction "P$2_P$2") (pintype "passive"))
      (node (ref "C24") (pin "P$2") (pinfunction "P$2_P$2") (pintype "passive"))
      (node (ref "C25") (pin "P$2") (pinfunction "P$2_P$2") (pintype "passive"))
      (node (ref "C26") (pin "P$2") (pinfunction "P$2_P$2") (pintype "passive"))
      (node (ref "C27") (pin "P$2") (pinfunction "P$2_P$2") (pintype "passive"))
      (node (ref "C28") (pin "P$2") (pinfunction "P$2_P$2") (pintype "passive"))
      (node (ref "C29") (pin "P$2") (pinfunction "P$2_P$2") (pintype "passive"))
      (node (ref "C30") (pin "P$2") (pinfunction "P$2_P$2") (pintype "passive"))
      (node (ref "C31") (pin "P$2") (pinfunction "P$2_P$2") (pintype "passive"))
      (node (ref "C32") (pin "P$2") (pinfunction "P$2_P$2") (pintype "passive"))
      (node (ref "C33") (pin "P$2") (pinfunction "P$2_P$2") (pintype "passive"))
      (node (ref "C34") (pin "P$2") (pinfunction "P$2_P$2") (pintype "passive"))
      (node (ref "C35") (pin "P$2") (pinfunction "P$2_P$2") (pintype "passive"))
      (node (ref "C36") (pin "P$2") (pinfunction "P$2_P$2") (pintype "passive"))
      (node (ref "C37") (pin "P$2") (pinfunction "P$2_P$2") (pintype "passive"))
      (node (ref "C38") (pin "P$1") (pinfunction "P$1_P$1") (pintype "passive"))
      (node (ref "C39") (pin "P$2") (pinfunction "P$2_P$2") (pintype "passive"))
      (node (ref "C40") (pin "P$2") (pinfunction "P$2_P$2") (pintype "passive"))
      (node (ref "C41") (pin "P$2") (pinfunction "P$2_P$2") (pintype "passive"))
      (node (ref "C42") (pin "P$2") (pinfunction "P$2_P$2") (pintype "passive"))
      (node (ref "C43") (pin "P$2") (pinfunction "P$2_P$2") (pintype "passive"))
      (node (ref "C44") (pin "P$2") (pinfunction "P$2_P$2") (pintype "passive"))
      (node (ref "C45") (pin "P$2") (pinfunction "P$2_P$2") (pintype "passive"))
      (node (ref "C46") (pin "P$2") (pinfunction "P$2_P$2") (pintype "passive"))
      (node (ref "C47") (pin "P$2") (pinfunction "P$2_P$2") (pintype "passive"))
      (node (ref "C48") (pin "P$2") (pinfunction "P$2_P$2") (pintype "passive"))
      (node (ref "C49") (pin "P$2") (pinfunction "P$2_P$2") (pintype "passive"))
      (node (ref "C50") (pin "P$2") (pinfunction "P$2_P$2") (pintype "passive"))
      (node (ref "C51") (pin "P$2") (pinfunction "P$2_P$2") (pintype "passive"))
      (node (ref "C52") (pin "P$2") (pinfunction "P$2_P$2") (pintype "passive"))
      (node (ref "C53") (pin "P$2") (pinfunction "P$2_P$2") (pintype "passive"))
      (node (ref "C54") (pin "P$2") (pinfunction "P$2_P$2") (pintype "passive"))
      (node (ref "C55") (pin "P$2") (pinfunction "P$2_P$2") (pintype "passive"))
      (node (ref "J1") (pin "2") (pinfunction "2_2") (pintype "passive"))
      (node (ref "J2") (pin "2") (pinfunction "2_2") (pintype "passive"))
      (node (ref "R10") (pin "P$2") (pinfunction "P$2_P$2") (pintype "passive"))
      (node (ref "RA") (pin "1") (pinfunction "1_1") (pintype "passive"))
      (node (ref "RB") (pin "1") (pinfunction "1_1") (pintype "passive"))
      (node (ref "RC") (pin "1") (pinfunction "1_1") (pintype "passive"))
      (node (ref "SH1") (pin "2") (pinfunction "P$2_2") (pintype "bidirectional"))
      (node (ref "SH2") (pin "2") (pinfunction "P$2_2") (pintype "bidirectional"))
      (node (ref "SH3") (pin "2") (pinfunction "P$2_2") (pintype "bidirectional"))
      (node (ref "SH4") (pin "1") (pinfunction "P$1_1") (pintype "bidirectional"))
      (node (ref "U5") (pin "39") (pinfunction "GND_39") (pintype "bidirectional"))
      (node (ref "U5") (pin "P1") (pinfunction "PAD_P1") (pintype "bidirectional"))
      (node (ref "U5") (pin "P12") (pinfunction "PAD_P12") (pintype "bidirectional"))
      (node (ref "U5") (pin "P13") (pinfunction "PAD_P13") (pintype "bidirectional"))
      (node (ref "U5") (pin "P14") (pinfunction "PAD_P14") (pintype "bidirectional"))
      (node (ref "U5") (pin "P17") (pinfunction "PAD_P17") (pintype "bidirectional"))
      (node (ref "U5") (pin "P18") (pinfunction "PAD_P18") (pintype "bidirectional"))
      (node (ref "U5") (pin "P19") (pinfunction "PAD_P19") (pintype "bidirectional"))
      (node (ref "U5") (pin "P2") (pinfunction "PAD_P2") (pintype "bidirectional"))
      (node (ref "U5") (pin "P3") (pinfunction "PAD_P3") (pintype "bidirectional"))
      (node (ref "U5") (pin "P7") (pinfunction "PAD_P7") (pintype "bidirectional"))
      (node (ref "U5") (pin "P8") (pinfunction "PAD_P8") (pintype "bidirectional"))
      (node (ref "U5") (pin "P9") (pinfunction "PAD_P9") (pintype "bidirectional"))
      (node (ref "U5") (pin "PAD") (pinfunction "PAD_PAD") (pintype "bidirectional"))
    )
    (net (code "71") (name "unconnected-(M1-PadP$1)") (class "Default")
      (node (ref "M1") (pin "P$1") (pinfunction "P$1_P$1") (pintype "bidirectional"))
    )
    (net (code "72") (name "unconnected-(M2-PadP$1)") (class "Default")
      (node (ref "M2") (pin "P$1") (pinfunction "P$1_P$1") (pintype "bidirectional"))
    )
    (net (code "73") (name "unconnected-(M4-PadP$1)") (class "Default")
      (node (ref "M4") (pin "P$1") (pinfunction "P$1_P$1") (pintype "bidirectional"))
    )
    (net (code "74") (name "unconnected-(SWD-Pad1)") (class "Default")
      (node (ref "SWD") (pin "1") (pinfunction "1_1") (pintype "passive"))
    )
    (net (code "75") (name "unconnected-(U1-PA10-Pad32)") (class "Default")
      (node (ref "U1") (pin "32") (pinfunction "PA10_32") (pintype "bidirectional"))
    )
    (net (code "76") (name "unconnected-(U1-PB3-Pad41)") (class "Default")
      (node (ref "U1") (pin "41") (pinfunction "PB3_41") (pintype "bidirectional"))
    )
    (net (code "77") (name "unconnected-(U1-PB10-Pad22)") (class "Default")
      (node (ref "U1") (pin "22") (pinfunction "PB10_22") (pintype "bidirectional"))
    )
    (net (code "78") (name "unconnected-(U3-I-Pad14)") (class "Default")
      (node (ref "U3") (pin "14") (pinfunction "I_14") (pintype "bidirectional"))
    )
    (net (code "79") (name "unconnected-(U3-PWM-Pad8)") (class "Default")
      (node (ref "U3") (pin "8") (pinfunction "PWM_8") (pintype "bidirectional"))
    )
    (net (code "80") (name "unconnected-(U3-VDD5V-Pad11)") (class "Default")
      (node (ref "U3") (pin "11") (pinfunction "VDD5V_11") (pintype "bidirectional"))
    )
    (net (code "81") (name "unconnected-(U4-MODE-Pad5)") (class "Default")
      (node (ref "U4") (pin "5") (pinfunction "MODE_5") (pintype "input"))
    )
    (net (code "82") (name "unconnected-(U4-~{RESET}-Pad6)") (class "Default")
      (node (ref "U4") (pin "6") (pinfunction "~{RESET}_6") (pintype "output"))
    )
  )
)
